# BatteryBoardV1.net
KiCad netlist of a schematic drawn in EAGLE
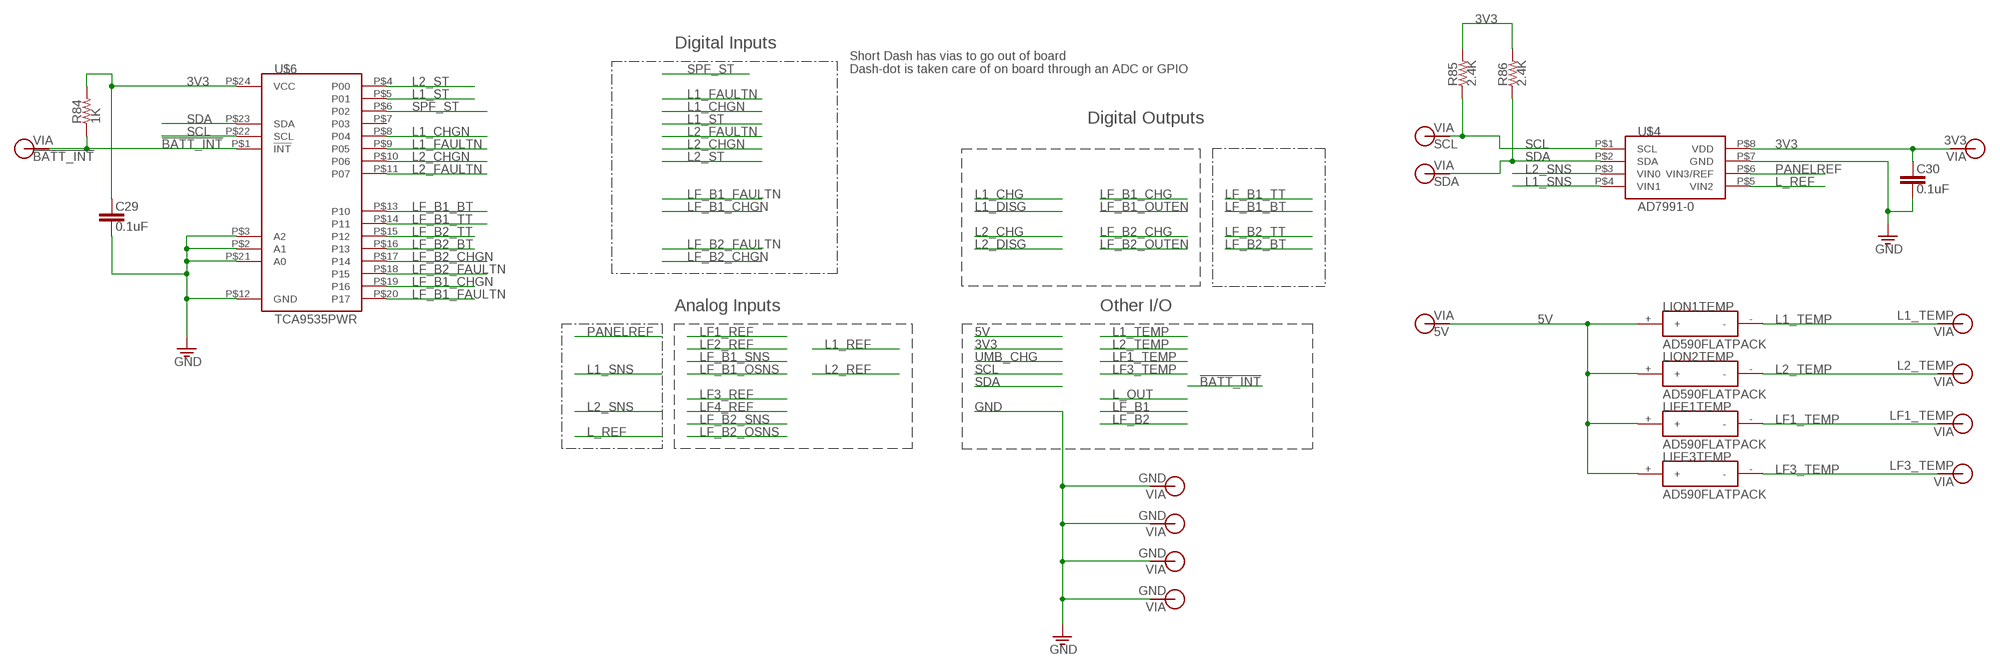
[diagram p0: schematic, sheet 1]
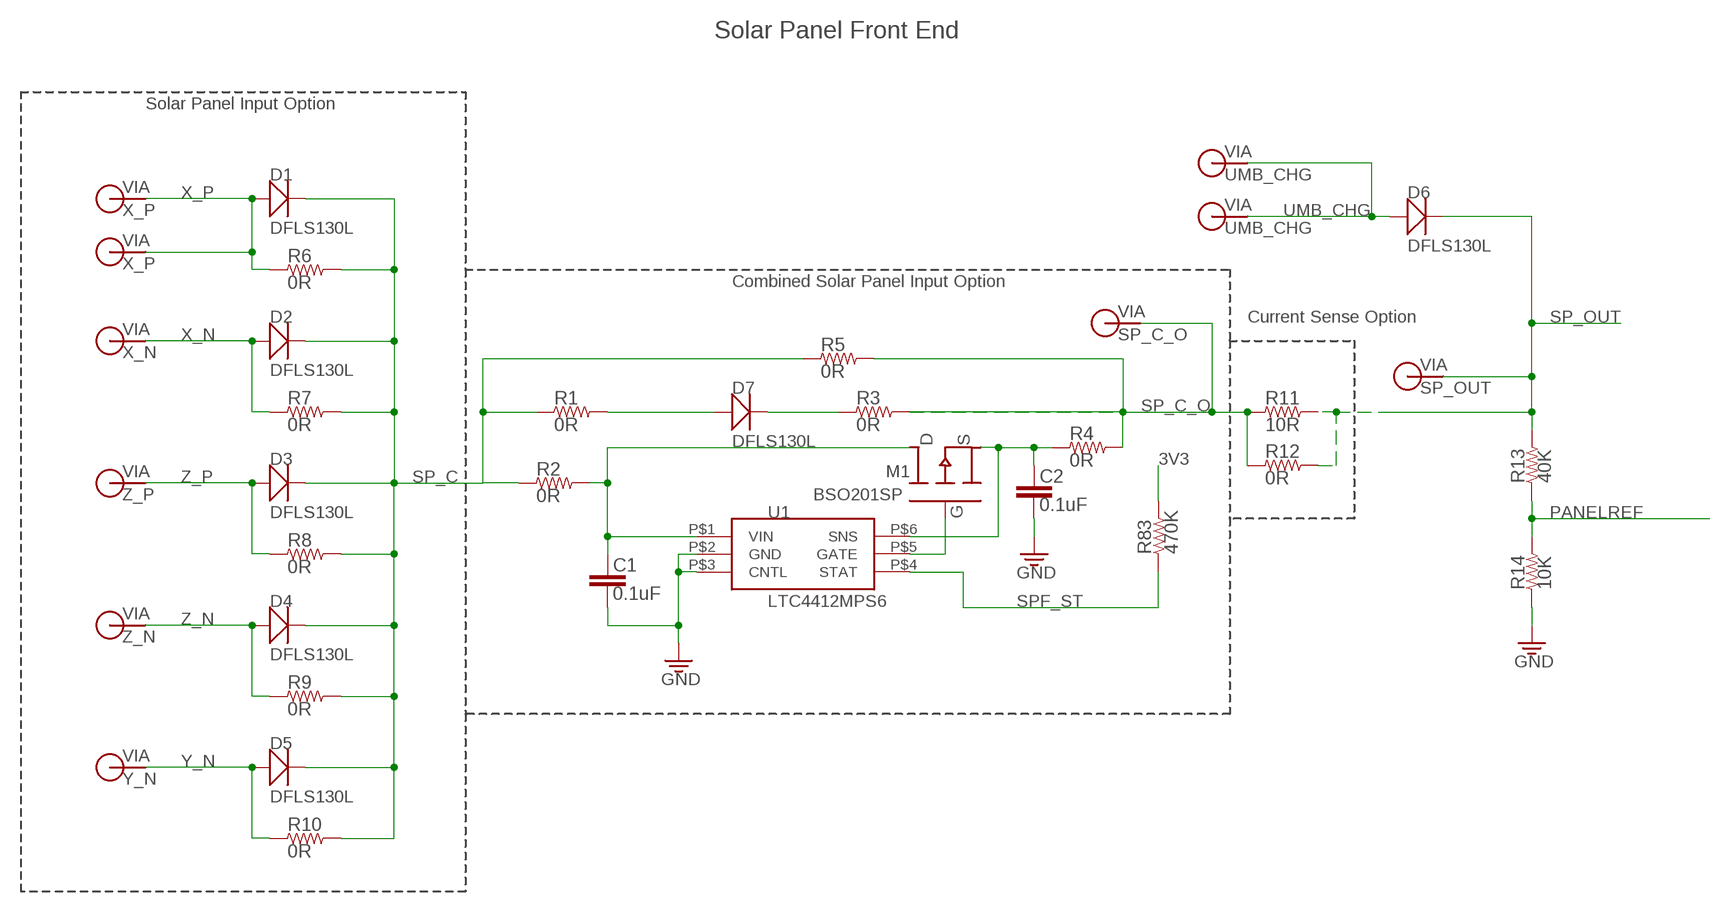
[diagram p1: schematic, sheet 2]
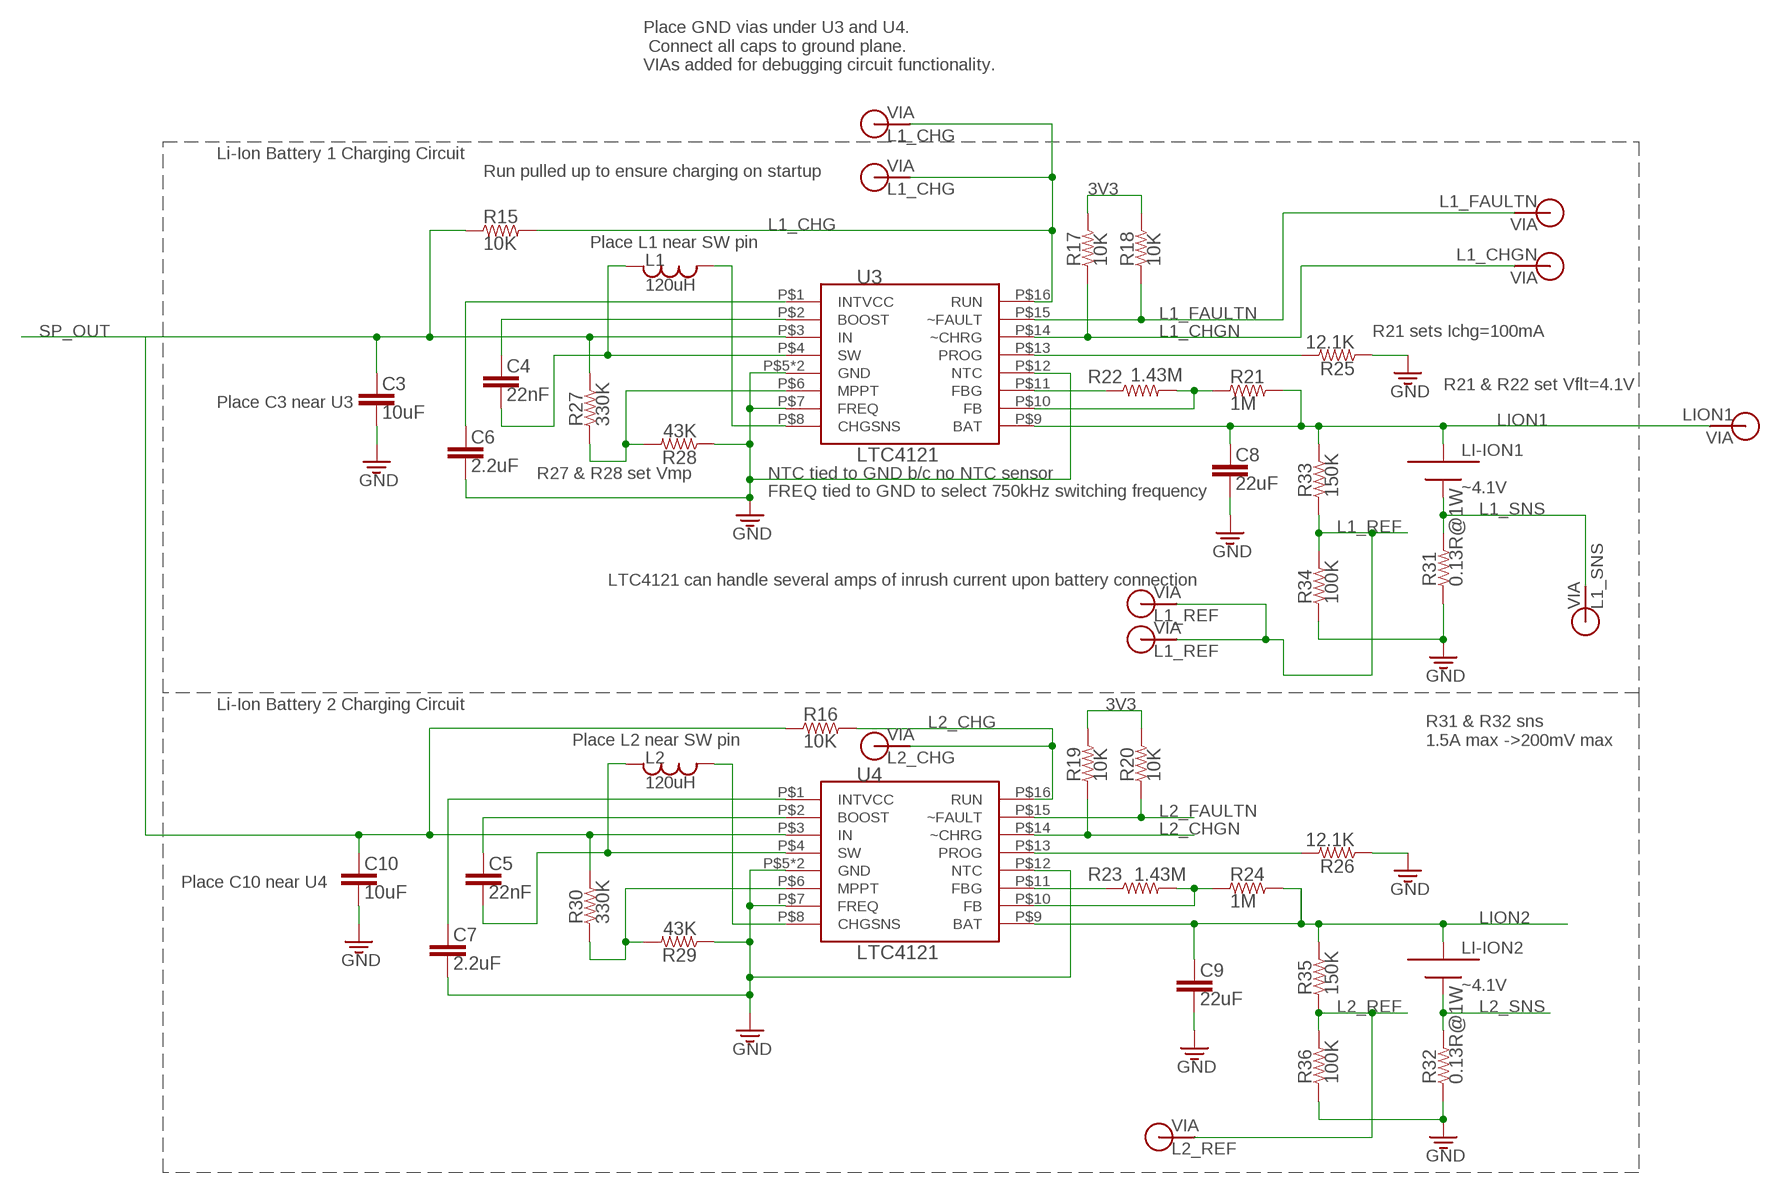
[diagram p2: schematic, sheet 3]
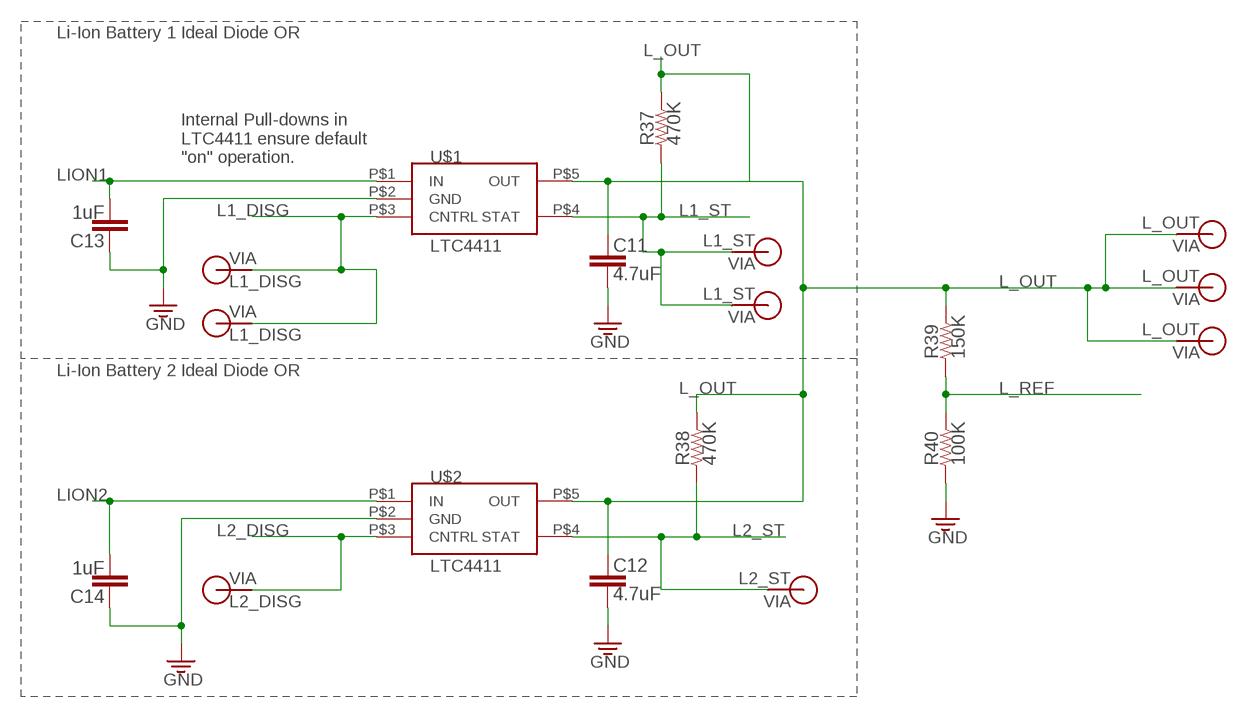
[diagram p3: schematic, sheet 4]
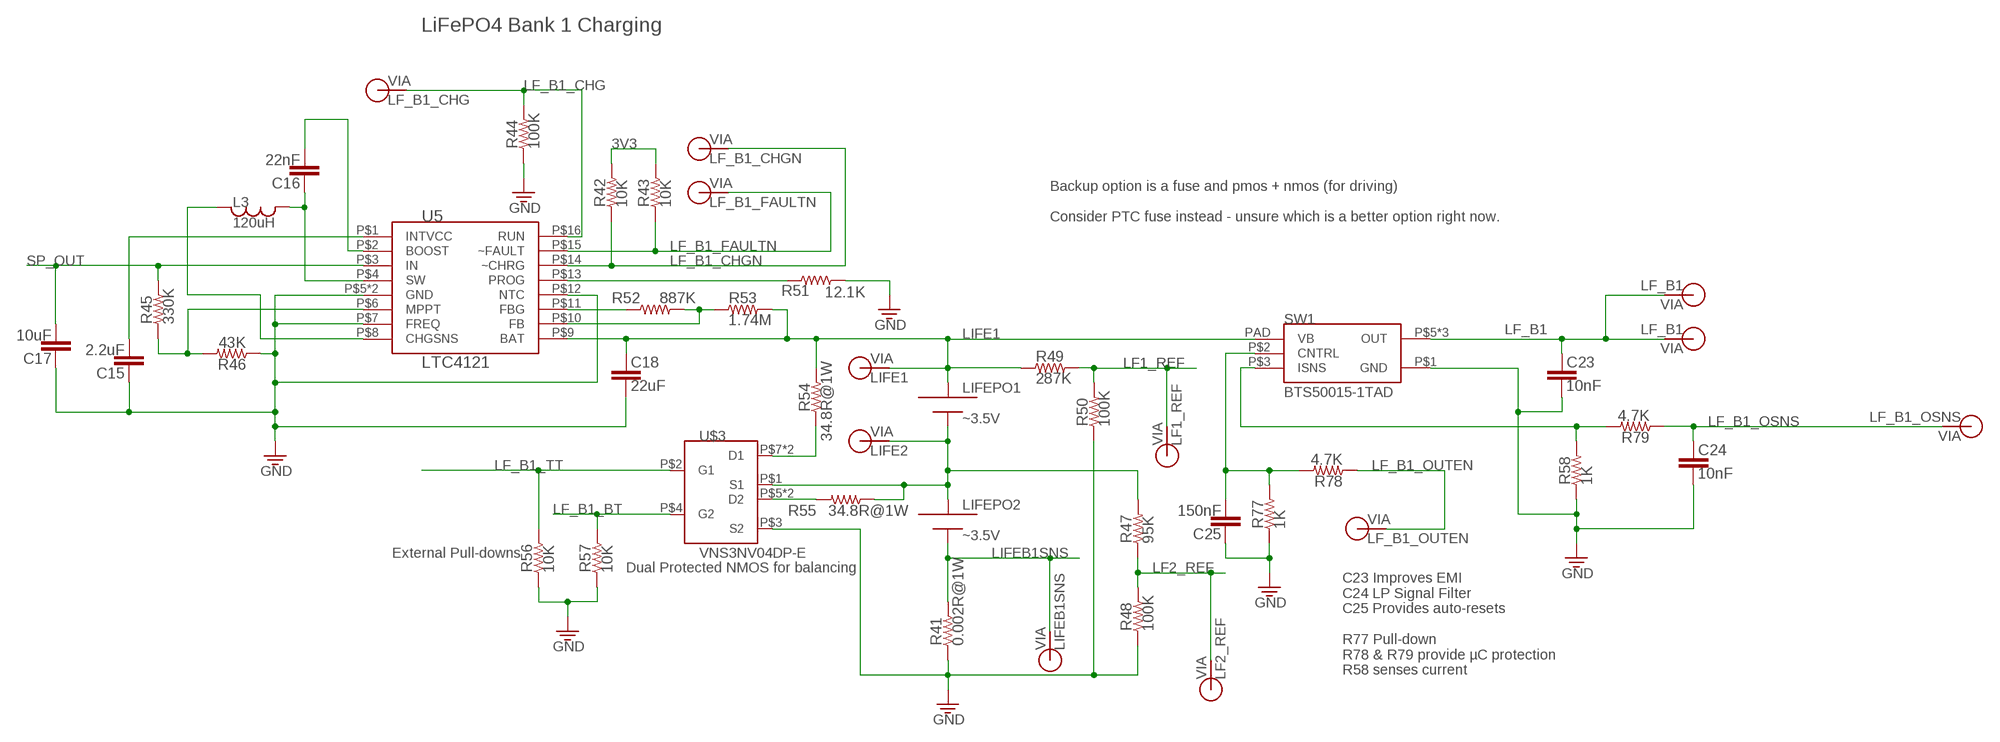
[diagram p4: schematic, sheet 5]
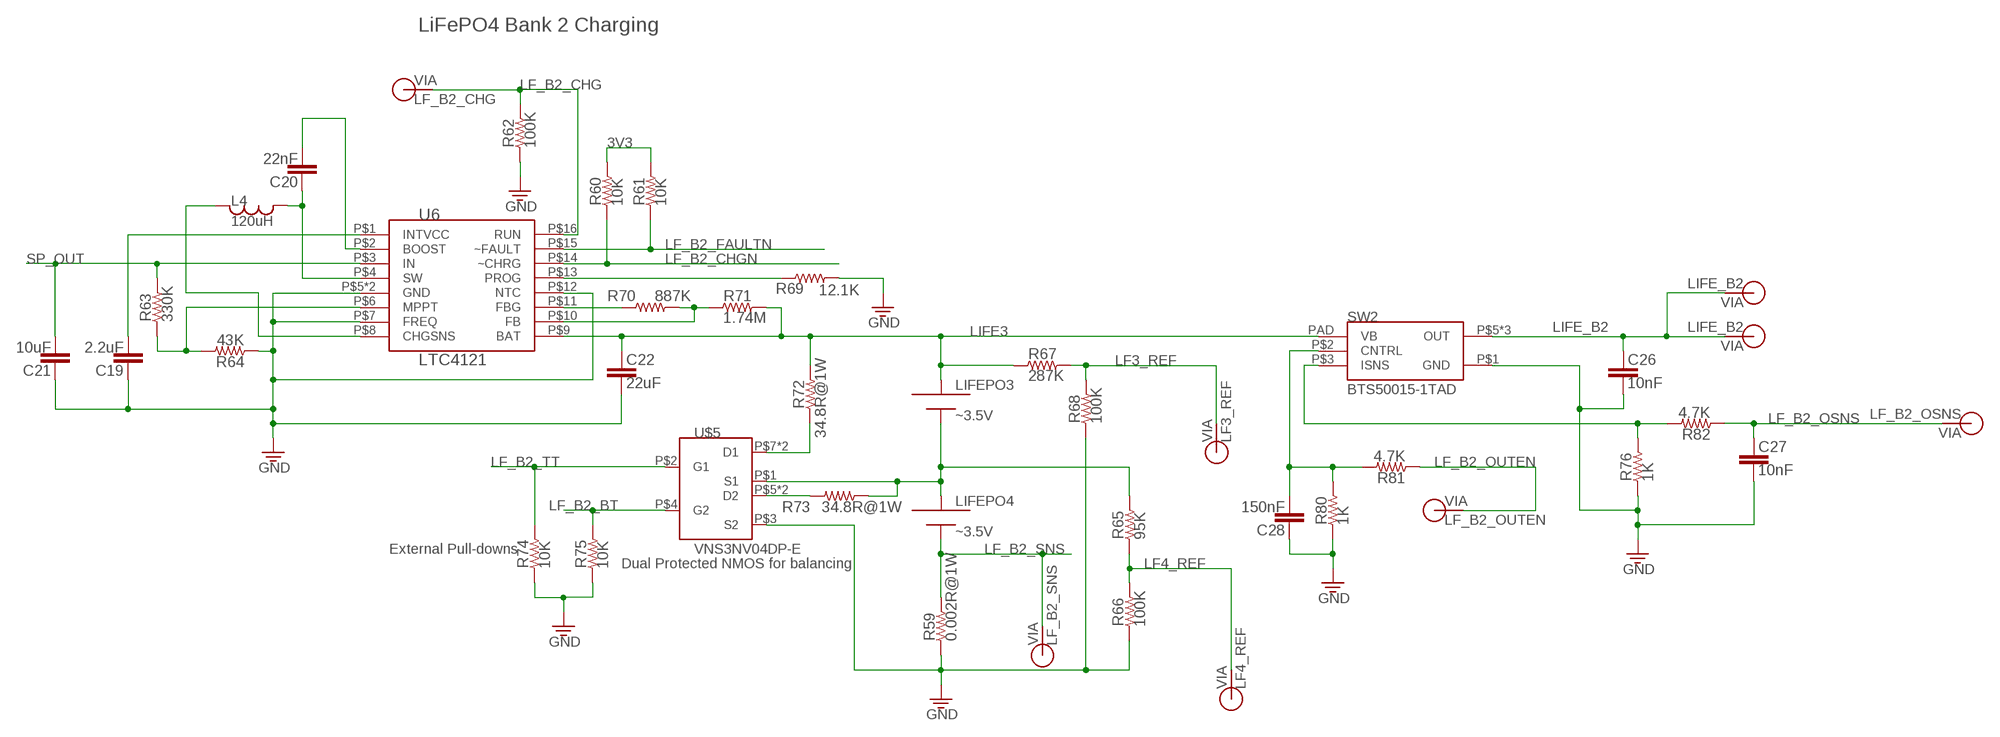
[diagram p5: schematic, sheet 6]

(export (version "E")
  (design (tool "Eeschema 10.0.6"))
  (components
    (comp (ref "C15")
      (value "2.2uF")
      (footprint "eagle-import:0805")
      (libsource (lib "eagle-import") (part "CAP0805"))
    )
    (comp (ref "C16")
      (value "22nF")
      (footprint "eagle-import:0805")
      (libsource (lib "eagle-import") (part "CAP0805"))
    )
    (comp (ref "C17")
      (value "10uF")
      (footprint "eagle-import:0805")
      (libsource (lib "eagle-import") (part "CAP0805"))
    )
    (comp (ref "C18")
      (value "22uF")
      (footprint "eagle-import:0805")
      (libsource (lib "eagle-import") (part "CAP0805"))
    )
    (comp (ref "C23")
      (value "10nF")
      (footprint "eagle-import:0805")
      (libsource (lib "eagle-import") (part "CAP0805"))
    )
    (comp (ref "C24")
      (value "10nF")
      (footprint "eagle-import:0805")
      (libsource (lib "eagle-import") (part "CAP0805"))
    )
    (comp (ref "C25")
      (value "150nF")
      (footprint "eagle-import:0805")
      (libsource (lib "eagle-import") (part "CAP0805"))
    )
    (comp (ref "L3")
      (value "120uH")
      (footprint "eagle-import:1812")
      (libsource (lib "eagle-import") (part "IND1812"))
    )
    (comp (ref "LIFEPO1")
      (value "~3.5V")
      (footprint "eagle-import:EQUISAT-BATTERY-VA")
      (libsource (lib "eagle-import") (part "LIFEPO4VA"))
    )
    (comp (ref "LIFEPO2")
      (value "~3.5V")
      (footprint "eagle-import:EQUISAT-BATTERY-VB")
      (libsource (lib "eagle-import") (part "LIFEPO4VB"))
    )
    (comp (ref "R41")
      (value "0.002R@1W")
      (footprint "eagle-import:1210")
      (libsource (lib "eagle-import") (part "RES1210"))
    )
    (comp (ref "R42")
      (value "10K")
      (footprint "eagle-import:0805")
      (libsource (lib "eagle-import") (part "RES0805"))
    )
    (comp (ref "R43")
      (value "10K")
      (footprint "eagle-import:0805")
      (libsource (lib "eagle-import") (part "RES0805"))
    )
    (comp (ref "R44")
      (value "100K")
      (footprint "eagle-import:0805")
      (libsource (lib "eagle-import") (part "RES0805"))
    )
    (comp (ref "R45")
      (value "330K")
      (footprint "eagle-import:0805")
      (libsource (lib "eagle-import") (part "RES0805"))
    )
    (comp (ref "R46")
      (value "43K")
      (footprint "eagle-import:0805")
      (libsource (lib "eagle-import") (part "RES0805"))
    )
    (comp (ref "R47")
      (value "95K")
      (footprint "eagle-import:0805")
      (libsource (lib "eagle-import") (part "RES0805"))
    )
    (comp (ref "R48")
      (value "100K")
      (footprint "eagle-import:0805")
      (libsource (lib "eagle-import") (part "RES0805"))
    )
    (comp (ref "R49")
      (value "287K")
      (footprint "eagle-import:0805")
      (libsource (lib "eagle-import") (part "RES0805"))
    )
    (comp (ref "R50")
      (value "100K")
      (footprint "eagle-import:0805")
      (libsource (lib "eagle-import") (part "RES0805"))
    )
    (comp (ref "R51")
      (value "12.1K")
      (footprint "eagle-import:0805")
      (libsource (lib "eagle-import") (part "RES0805"))
    )
    (comp (ref "R52")
      (value "887K")
      (footprint "eagle-import:0805")
      (libsource (lib "eagle-import") (part "RES0805"))
    )
    (comp (ref "R53")
      (value "1.74M")
      (footprint "eagle-import:0805")
      (libsource (lib "eagle-import") (part "RES0805"))
    )
    (comp (ref "R54")
      (value "34.8R@1W")
      (footprint "eagle-import:1210")
      (libsource (lib "eagle-import") (part "RES1210"))
    )
    (comp (ref "R55")
      (value "34.8R@1W")
      (footprint "eagle-import:1210")
      (libsource (lib "eagle-import") (part "RES1210"))
    )
    (comp (ref "R56")
      (value "10K")
      (footprint "eagle-import:0805")
      (libsource (lib "eagle-import") (part "RES0805"))
    )
    (comp (ref "R57")
      (value "10K")
      (footprint "eagle-import:0805")
      (libsource (lib "eagle-import") (part "RES0805"))
    )
    (comp (ref "R58")
      (value "1K")
      (footprint "eagle-import:0805")
      (libsource (lib "eagle-import") (part "RES0805"))
    )
    (comp (ref "R77")
      (value "1K")
      (footprint "eagle-import:0805")
      (libsource (lib "eagle-import") (part "RES0805"))
    )
    (comp (ref "R78")
      (value "4.7K")
      (footprint "eagle-import:0805")
      (libsource (lib "eagle-import") (part "RES0805"))
    )
    (comp (ref "R79")
      (value "4.7K")
      (footprint "eagle-import:0805")
      (libsource (lib "eagle-import") (part "RES0805"))
    )
    (comp (ref "SW1")
      (value "BTS50015-1TAD")
      (footprint "eagle-import:TO-263-7-8")
      (libsource (lib "eagle-import") (part "BTS50015-1TAD"))
    )
    (comp (ref "U$3")
      (value "VNS3NV04DP-E")
      (footprint "eagle-import:SO-8")
      (libsource (lib "eagle-import") (part "VNS3NV04DP-E"))
    )
    (comp (ref "U5")
      (value "LTC4121")
      (footprint "eagle-import:QFN-16-PAD")
      (libsource (lib "eagle-import") (part "LTC4121"))
    )
    (comp (ref "V14")
      (value "LIFEB1SNS")
      (footprint "eagle-import:VIA-60MIL")
      (libsource (lib "eagle-import") (part "VIA-60MIL"))
    )
    (comp (ref "V15")
      (value "LF_B1_CHG")
      (footprint "eagle-import:VIA-60MIL")
      (libsource (lib "eagle-import") (part "VIA-60MIL"))
    )
    (comp (ref "V16")
      (value "LIFE2")
      (footprint "eagle-import:VIA-60MIL-SQ")
      (libsource (lib "eagle-import") (part "VIA60MIL-SQ"))
    )
    (comp (ref "V17")
      (value "LIFE1")
      (footprint "eagle-import:VIA-60MIL-SQ")
      (libsource (lib "eagle-import") (part "VIA60MIL-SQ"))
    )
    (comp (ref "V18")
      (value "LF_B1_CHGN")
      (footprint "eagle-import:VIA-60MIL")
      (libsource (lib "eagle-import") (part "VIA-60MIL"))
    )
    (comp (ref "V19")
      (value "LF_B1_FAULTN")
      (footprint "eagle-import:VIA-60MIL")
      (libsource (lib "eagle-import") (part "VIA-60MIL"))
    )
    (comp (ref "V20")
      (value "LF_B1_OUTEN")
      (footprint "eagle-import:VIA-60MIL")
      (libsource (lib "eagle-import") (part "VIA-60MIL"))
    )
    (comp (ref "V21")
      (value "LF_B1")
      (footprint "eagle-import:VIA-120MIL")
      (libsource (lib "eagle-import") (part "VIA-120MIL"))
    )
    (comp (ref "V26")
      (value "LF_B1")
      (footprint "eagle-import:VIA-120MIL")
      (libsource (lib "eagle-import") (part "VIA-120MIL"))
    )
    (comp (ref "V31")
      (value "LF_B1_OSNS")
      (footprint "eagle-import:VIA-60MIL")
      (libsource (lib "eagle-import") (part "VIA-60MIL"))
    )
    (comp (ref "V58")
      (value "LF1_REF")
      (footprint "eagle-import:VIA-60MIL")
      (libsource (lib "eagle-import") (part "VIA-60MIL"))
    )
    (comp (ref "V59")
      (value "LF2_REF")
      (footprint "eagle-import:VIA-60MIL")
      (libsource (lib "eagle-import") (part "VIA-60MIL"))
    )
    (comp (ref "C11")
      (value "4.7uF")
      (footprint "eagle-import:0805")
      (libsource (lib "eagle-import") (part "CAP0805"))
    )
    (comp (ref "C12")
      (value "4.7uF")
      (footprint "eagle-import:0805")
      (libsource (lib "eagle-import") (part "CAP0805"))
    )
    (comp (ref "C13")
      (value "1uF")
      (footprint "eagle-import:0805")
      (libsource (lib "eagle-import") (part "CAP0805"))
    )
    (comp (ref "C14")
      (value "1uF")
      (footprint "eagle-import:0805")
      (libsource (lib "eagle-import") (part "CAP0805"))
    )
    (comp (ref "R37")
      (value "470K")
      (footprint "eagle-import:0805")
      (libsource (lib "eagle-import") (part "RES0805"))
    )
    (comp (ref "R38")
      (value "470K")
      (footprint "eagle-import:0805")
      (libsource (lib "eagle-import") (part "RES0805"))
    )
    (comp (ref "R39")
      (value "150K")
      (footprint "eagle-import:0805")
      (libsource (lib "eagle-import") (part "RES0805"))
    )
    (comp (ref "R40")
      (value "100K")
      (footprint "eagle-import:0805")
      (libsource (lib "eagle-import") (part "RES0805"))
    )
    (comp (ref "U$1")
      (value "LTC4411")
      (footprint "eagle-import:TSOT23-5")
      (libsource (lib "eagle-import") (part "LTC4411"))
    )
    (comp (ref "U$2")
      (value "LTC4411")
      (footprint "eagle-import:TSOT23-5")
      (libsource (lib "eagle-import") (part "LTC4411"))
    )
    (comp (ref "V30")
      (value "L_OUT")
      (footprint "eagle-import:VIA-120MIL")
      (libsource (lib "eagle-import") (part "VIA-120MIL"))
    )
    (comp (ref "V34")
      (value "L1_DISG")
      (footprint "eagle-import:VIA-60MIL")
      (libsource (lib "eagle-import") (part "VIA-60MIL"))
    )
    (comp (ref "V35")
      (value "L2_DISG")
      (footprint "eagle-import:VIA-60MIL")
      (libsource (lib "eagle-import") (part "VIA-60MIL"))
    )
    (comp (ref "V36")
      (value "L1_ST")
      (footprint "eagle-import:VIA-60MIL")
      (libsource (lib "eagle-import") (part "VIA-60MIL"))
    )
    (comp (ref "V38")
      (value "L2_ST")
      (footprint "eagle-import:VIA-60MIL")
      (libsource (lib "eagle-import") (part "VIA-60MIL"))
    )
    (comp (ref "V46")
      (value "L1_DISG")
      (footprint "eagle-import:VIA-60MIL-SQ")
      (libsource (lib "eagle-import") (part "VIA60MIL-SQ"))
    )
    (comp (ref "V47")
      (value "L1_ST")
      (footprint "eagle-import:VIA-60MIL-SQ")
      (libsource (lib "eagle-import") (part "VIA60MIL-SQ"))
    )
    (comp (ref "V48")
      (value "L_OUT")
      (footprint "eagle-import:VIA-60MIL-SQ")
      (libsource (lib "eagle-import") (part "VIA60MIL-SQ"))
    )
    (comp (ref "V54")
      (value "L_OUT")
      (footprint "eagle-import:VIA-120MIL")
      (libsource (lib "eagle-import") (part "VIA-120MIL"))
    )
    (comp (ref "C1")
      (value "0.1uF")
      (footprint "eagle-import:0805")
      (libsource (lib "eagle-import") (part "CAP0805"))
    )
    (comp (ref "C2")
      (value "0.1uF")
      (footprint "eagle-import:0805")
      (libsource (lib "eagle-import") (part "CAP0805"))
    )
    (comp (ref "D1")
      (value "DFLS130L")
      (footprint "eagle-import:PWRDI-123")
      (libsource (lib "eagle-import") (part "DFLS130L"))
    )
    (comp (ref "D2")
      (value "DFLS130L")
      (footprint "eagle-import:PWRDI-123")
      (libsource (lib "eagle-import") (part "DFLS130L"))
    )
    (comp (ref "D3")
      (value "DFLS130L")
      (footprint "eagle-import:PWRDI-123")
      (libsource (lib "eagle-import") (part "DFLS130L"))
    )
    (comp (ref "D4")
      (value "DFLS130L")
      (footprint "eagle-import:PWRDI-123")
      (libsource (lib "eagle-import") (part "DFLS130L"))
    )
    (comp (ref "D5")
      (value "DFLS130L")
      (footprint "eagle-import:PWRDI-123")
      (libsource (lib "eagle-import") (part "DFLS130L"))
    )
    (comp (ref "D6")
      (value "DFLS130L")
      (footprint "eagle-import:PWRDI-123")
      (libsource (lib "eagle-import") (part "DFLS130L"))
    )
    (comp (ref "D7")
      (value "DFLS130L")
      (footprint "eagle-import:PWRDI-123")
      (libsource (lib "eagle-import") (part "DFLS130L"))
    )
    (comp (ref "M1")
      (value "BSO201SP")
      (footprint "eagle-import:SO-8")
      (libsource (lib "eagle-import") (part "BSO201SP"))
    )
    (comp (ref "R1")
      (value "0R")
      (footprint "eagle-import:0805")
      (libsource (lib "eagle-import") (part "RES0805"))
    )
    (comp (ref "R2")
      (value "0R")
      (footprint "eagle-import:0805")
      (libsource (lib "eagle-import") (part "RES0805"))
    )
    (comp (ref "R3")
      (value "0R")
      (footprint "eagle-import:0805")
      (libsource (lib "eagle-import") (part "RES0805"))
    )
    (comp (ref "R4")
      (value "0R")
      (footprint "eagle-import:0805")
      (libsource (lib "eagle-import") (part "RES0805"))
    )
    (comp (ref "R5")
      (value "0R")
      (footprint "eagle-import:0805")
      (libsource (lib "eagle-import") (part "RES0805"))
    )
    (comp (ref "R6")
      (value "0R")
      (footprint "eagle-import:0805")
      (libsource (lib "eagle-import") (part "RES0805"))
    )
    (comp (ref "R7")
      (value "0R")
      (footprint "eagle-import:0805")
      (libsource (lib "eagle-import") (part "RES0805"))
    )
    (comp (ref "R8")
      (value "0R")
      (footprint "eagle-import:0805")
      (libsource (lib "eagle-import") (part "RES0805"))
    )
    (comp (ref "R9")
      (value "0R")
      (footprint "eagle-import:0805")
      (libsource (lib "eagle-import") (part "RES0805"))
    )
    (comp (ref "R10")
      (value "0R")
      (footprint "eagle-import:0805")
      (libsource (lib "eagle-import") (part "RES0805"))
    )
    (comp (ref "R11")
      (value "10R")
      (footprint "eagle-import:0805")
      (libsource (lib "eagle-import") (part "RES0805"))
    )
    (comp (ref "R12")
      (value "0R")
      (footprint "eagle-import:0805")
      (libsource (lib "eagle-import") (part "RES0805"))
    )
    (comp (ref "R13")
      (value "40K")
      (footprint "eagle-import:0805")
      (libsource (lib "eagle-import") (part "RES0805"))
    )
    (comp (ref "R14")
      (value "10K")
      (footprint "eagle-import:0805")
      (libsource (lib "eagle-import") (part "RES0805"))
    )
    (comp (ref "R83")
      (value "470K")
      (footprint "eagle-import:0805")
      (libsource (lib "eagle-import") (part "RES0805"))
    )
    (comp (ref "U1")
      (value "LTC4412MPS6")
      (footprint "eagle-import:TSOT23-6")
      (libsource (lib "eagle-import") (part "LTC4412"))
    )
    (comp (ref "V1")
      (value "UMB_CHG")
      (footprint "eagle-import:VIA-60MIL")
      (libsource (lib "eagle-import") (part "VIA-60MIL"))
    )
    (comp (ref "V2")
      (value "X_P")
      (footprint "eagle-import:VIA-60MIL")
      (libsource (lib "eagle-import") (part "VIA-60MIL"))
    )
    (comp (ref "V3")
      (value "X_N")
      (footprint "eagle-import:VIA-60MIL")
      (libsource (lib "eagle-import") (part "VIA-60MIL"))
    )
    (comp (ref "V4")
      (value "Z_P")
      (footprint "eagle-import:VIA-60MIL")
      (libsource (lib "eagle-import") (part "VIA-60MIL"))
    )
    (comp (ref "V5")
      (value "Z_N")
      (footprint "eagle-import:VIA-60MIL")
      (libsource (lib "eagle-import") (part "VIA-60MIL"))
    )
    (comp (ref "V6")
      (value "Y_N")
      (footprint "eagle-import:VIA-60MIL")
      (libsource (lib "eagle-import") (part "VIA-60MIL"))
    )
    (comp (ref "V7")
      (value "SP_C_O")
      (footprint "eagle-import:VIA-60MIL-SQ")
      (libsource (lib "eagle-import") (part "VIA60MIL-SQ"))
    )
    (comp (ref "V8")
      (value "SP_OUT")
      (footprint "eagle-import:VIA-60MIL-SQ")
      (libsource (lib "eagle-import") (part "VIA60MIL-SQ"))
    )
    (comp (ref "V39")
      (value "UMB_CHG")
      (footprint "eagle-import:VIA-60MIL-SQ")
      (libsource (lib "eagle-import") (part "VIA60MIL-SQ"))
    )
    (comp (ref "V49")
      (value "X_P")
      (footprint "eagle-import:VIA-60MIL-SQ")
      (libsource (lib "eagle-import") (part "VIA60MIL-SQ"))
    )
    (comp (ref "C3")
      (value "10uF")
      (footprint "eagle-import:0805")
      (libsource (lib "eagle-import") (part "CAP0805"))
    )
    (comp (ref "C4")
      (value "22nF")
      (footprint "eagle-import:0805")
      (libsource (lib "eagle-import") (part "CAP0805"))
    )
    (comp (ref "C5")
      (value "22nF")
      (footprint "eagle-import:0805")
      (libsource (lib "eagle-import") (part "CAP0805"))
    )
    (comp (ref "C6")
      (value "2.2uF")
      (footprint "eagle-import:0805")
      (libsource (lib "eagle-import") (part "CAP0805"))
    )
    (comp (ref "C7")
      (value "2.2uF")
      (footprint "eagle-import:0805")
      (libsource (lib "eagle-import") (part "CAP0805"))
    )
    (comp (ref "C8")
      (value "22uF")
      (footprint "eagle-import:0805")
      (libsource (lib "eagle-import") (part "CAP0805"))
    )
    (comp (ref "C9")
      (value "22uF")
      (footprint "eagle-import:0805")
      (libsource (lib "eagle-import") (part "CAP0805"))
    )
    (comp (ref "C10")
      (value "10uF")
      (footprint "eagle-import:0805")
      (libsource (lib "eagle-import") (part "CAP0805"))
    )
    (comp (ref "L1")
      (value "120uH")
      (footprint "eagle-import:1812")
      (libsource (lib "eagle-import") (part "IND1812"))
    )
    (comp (ref "L2")
      (value "120uH")
      (footprint "eagle-import:1812")
      (libsource (lib "eagle-import") (part "IND1812"))
    )
    (comp (ref "LI-ION1")
      (value "~4.1V")
      (footprint "eagle-import:EQUISAT-BATTERY-VA")
      (libsource (lib "eagle-import") (part "LI-ION"))
    )
    (comp (ref "LI-ION2")
      (value "~4.1V")
      (footprint "eagle-import:EQUISAT-BATTERY-VA")
      (libsource (lib "eagle-import") (part "LI-ION"))
    )
    (comp (ref "R15")
      (value "10K")
      (footprint "eagle-import:0805")
      (libsource (lib "eagle-import") (part "RES0805"))
    )
    (comp (ref "R16")
      (value "10K")
      (footprint "eagle-import:0805")
      (libsource (lib "eagle-import") (part "RES0805"))
    )
    (comp (ref "R17")
      (value "10K")
      (footprint "eagle-import:0805")
      (libsource (lib "eagle-import") (part "RES0805"))
    )
    (comp (ref "R18")
      (value "10K")
      (footprint "eagle-import:0805")
      (libsource (lib "eagle-import") (part "RES0805"))
    )
    (comp (ref "R19")
      (value "10K")
      (footprint "eagle-import:0805")
      (libsource (lib "eagle-import") (part "RES0805"))
    )
    (comp (ref "R20")
      (value "10K")
      (footprint "eagle-import:0805")
      (libsource (lib "eagle-import") (part "RES0805"))
    )
    (comp (ref "R21")
      (value "1M")
      (footprint "eagle-import:0805")
      (libsource (lib "eagle-import") (part "RES0805"))
    )
    (comp (ref "R22")
      (value "1.43M")
      (footprint "eagle-import:0805")
      (libsource (lib "eagle-import") (part "RES0805"))
    )
    (comp (ref "R23")
      (value "1.43M")
      (footprint "eagle-import:0805")
      (libsource (lib "eagle-import") (part "RES0805"))
    )
    (comp (ref "R24")
      (value "1M")
      (footprint "eagle-import:0805")
      (libsource (lib "eagle-import") (part "RES0805"))
    )
    (comp (ref "R25")
      (value "12.1K")
      (footprint "eagle-import:0805")
      (libsource (lib "eagle-import") (part "RES0805"))
    )
    (comp (ref "R26")
      (value "12.1K")
      (footprint "eagle-import:0805")
      (libsource (lib "eagle-import") (part "RES0805"))
    )
    (comp (ref "R27")
      (value "330K")
      (footprint "eagle-import:0805")
      (libsource (lib "eagle-import") (part "RES0805"))
    )
    (comp (ref "R28")
      (value "43K")
      (footprint "eagle-import:0805")
      (libsource (lib "eagle-import") (part "RES0805"))
    )
    (comp (ref "R29")
      (value "43K")
      (footprint "eagle-import:0805")
      (libsource (lib "eagle-import") (part "RES0805"))
    )
    (comp (ref "R30")
      (value "330K")
      (footprint "eagle-import:0805")
      (libsource (lib "eagle-import") (part "RES0805"))
    )
    (comp (ref "R31")
      (value "0.13R@1W")
      (footprint "eagle-import:1210")
      (libsource (lib "eagle-import") (part "RES1210"))
    )
    (comp (ref "R32")
      (value "0.13R@1W")
      (footprint "eagle-import:1210")
      (libsource (lib "eagle-import") (part "RES1210"))
    )
    (comp (ref "R33")
      (value "150K")
      (footprint "eagle-import:0805")
      (libsource (lib "eagle-import") (part "RES0805"))
    )
    (comp (ref "R34")
      (value "100K")
      (footprint "eagle-import:0805")
      (libsource (lib "eagle-import") (part "RES0805"))
    )
    (comp (ref "R35")
      (value "150K")
      (footprint "eagle-import:0805")
      (libsource (lib "eagle-import") (part "RES0805"))
    )
    (comp (ref "R36")
      (value "100K")
      (footprint "eagle-import:0805")
      (libsource (lib "eagle-import") (part "RES0805"))
    )
    (comp (ref "U3")
      (value "LTC4121")
      (footprint "eagle-import:QFN-16-PAD")
      (libsource (lib "eagle-import") (part "LTC4121"))
    )
    (comp (ref "U4")
      (value "LTC4121")
      (footprint "eagle-import:QFN-16-PAD")
      (libsource (lib "eagle-import") (part "LTC4121"))
    )
    (comp (ref "V10")
      (value "L1_CHG")
      (footprint "eagle-import:VIA-60MIL")
      (libsource (lib "eagle-import") (part "VIA-60MIL"))
    )
    (comp (ref "V25")
      (value "L1_REF")
      (footprint "eagle-import:VIA-60MIL")
      (libsource (lib "eagle-import") (part "VIA-60MIL"))
    )
    (comp (ref "V29")
      (value "L2_REF")
      (footprint "eagle-import:VIA-60MIL")
      (libsource (lib "eagle-import") (part "VIA-60MIL"))
    )
    (comp (ref "V33")
      (value "L2_CHG")
      (footprint "eagle-import:VIA-60MIL")
      (libsource (lib "eagle-import") (part "VIA-60MIL"))
    )
    (comp (ref "V40")
      (value "L1_CHG")
      (footprint "eagle-import:VIA-60MIL-SQ")
      (libsource (lib "eagle-import") (part "VIA60MIL-SQ"))
    )
    (comp (ref "V41")
      (value "L1_FAULTN")
      (footprint "eagle-import:VIA-60MIL-SQ")
      (libsource (lib "eagle-import") (part "VIA60MIL-SQ"))
    )
    (comp (ref "V42")
      (value "L1_CHGN")
      (footprint "eagle-import:VIA-60MIL-SQ")
      (libsource (lib "eagle-import") (part "VIA60MIL-SQ"))
    )
    (comp (ref "V43")
      (value "L1_SNS")
      (footprint "eagle-import:VIA-60MIL-SQ")
      (libsource (lib "eagle-import") (part "VIA60MIL-SQ"))
    )
    (comp (ref "V44")
      (value "L1_REF")
      (footprint "eagle-import:VIA-60MIL-SQ")
      (libsource (lib "eagle-import") (part "VIA60MIL-SQ"))
    )
    (comp (ref "V45")
      (value "LION1")
      (footprint "eagle-import:VIA-60MIL-SQ")
      (libsource (lib "eagle-import") (part "VIA60MIL-SQ"))
    )
    (comp (ref "C29")
      (value "0.1uF")
      (footprint "eagle-import:0805")
      (libsource (lib "eagle-import") (part "CAP0805"))
    )
    (comp (ref "C30")
      (value "0.1uF")
      (footprint "eagle-import:0805")
      (libsource (lib "eagle-import") (part "CAP0805"))
    )
    (comp (ref "LIFE1TEMP")
      (value "AD590FLATPACK")
      (footprint "eagle-import:FLATPACK")
      (libsource (lib "eagle-import") (part "AD590FLATPACK"))
    )
    (comp (ref "LIFE3TEMP")
      (value "AD590FLATPACK")
      (footprint "eagle-import:FLATPACK")
      (libsource (lib "eagle-import") (part "AD590FLATPACK"))
    )
    (comp (ref "LION1TEMP")
      (value "AD590FLATPACK")
      (footprint "eagle-import:FLATPACK")
      (libsource (lib "eagle-import") (part "AD590FLATPACK"))
    )
    (comp (ref "LION2TEMP")
      (value "AD590FLATPACK")
      (footprint "eagle-import:FLATPACK")
      (libsource (lib "eagle-import") (part "AD590FLATPACK"))
    )
    (comp (ref "R84")
      (value "1K")
      (footprint "eagle-import:0805")
      (libsource (lib "eagle-import") (part "RES0805"))
    )
    (comp (ref "R85")
      (value "2.4K")
      (footprint "eagle-import:0805")
      (libsource (lib "eagle-import") (part "RES0805"))
    )
    (comp (ref "R86")
      (value "2.4K")
      (footprint "eagle-import:0805")
      (libsource (lib "eagle-import") (part "RES0805"))
    )
    (comp (ref "U$4")
      (value "AD7991-0")
      (footprint "eagle-import:SOT-23-8")
      (libsource (lib "eagle-import") (part "AD7991-0"))
    )
    (comp (ref "U$6")
      (value "TCA9535PWR")
      (footprint "eagle-import:TSSOP-24")
      (libsource (lib "eagle-import") (part "TCA9535PWR"))
    )
    (comp (ref "V9")
      (value "5V")
      (footprint "eagle-import:VIA-60MIL")
      (libsource (lib "eagle-import") (part "VIA-60MIL"))
    )
    (comp (ref "V11")
      (value "!BATT_INT!")
      (footprint "eagle-import:VIA-60MIL")
      (libsource (lib "eagle-import") (part "VIA-60MIL"))
    )
    (comp (ref "V12")
      (value "GND")
      (footprint "eagle-import:VIA-60MIL-SQ")
      (libsource (lib "eagle-import") (part "VIA60MIL-SQ"))
    )
    (comp (ref "V13")
      (value "GND")
      (footprint "eagle-import:VIA-120MIL")
      (libsource (lib "eagle-import") (part "VIA-120MIL"))
    )
    (comp (ref "V22")
      (value "GND")
      (footprint "eagle-import:VIA-120MIL")
      (libsource (lib "eagle-import") (part "VIA-120MIL"))
    )
    (comp (ref "V23")
      (value "GND")
      (footprint "eagle-import:VIA-120MIL")
      (libsource (lib "eagle-import") (part "VIA-120MIL"))
    )
    (comp (ref "V24")
      (value "L1_TEMP")
      (footprint "eagle-import:VIA-60MIL")
      (libsource (lib "eagle-import") (part "VIA-60MIL"))
    )
    (comp (ref "V32")
      (value "L2_TEMP")
      (footprint "eagle-import:VIA-60MIL")
      (libsource (lib "eagle-import") (part "VIA-60MIL"))
    )
    (comp (ref "V37")
      (value "LF1_TEMP")
      (footprint "eagle-import:VIA-60MIL")
      (libsource (lib "eagle-import") (part "VIA-60MIL"))
    )
    (comp (ref "V50")
      (value "LF3_TEMP")
      (footprint "eagle-import:VIA-60MIL")
      (libsource (lib "eagle-import") (part "VIA-60MIL"))
    )
    (comp (ref "V51")
      (value "3V3")
      (footprint "eagle-import:VIA-60MIL")
      (libsource (lib "eagle-import") (part "VIA-60MIL"))
    )
    (comp (ref "V52")
      (value "SCL")
      (footprint "eagle-import:VIA-60MIL")
      (libsource (lib "eagle-import") (part "VIA-60MIL"))
    )
    (comp (ref "V53")
      (value "SDA")
      (footprint "eagle-import:VIA-60MIL")
      (libsource (lib "eagle-import") (part "VIA-60MIL"))
    )
    (comp (ref "C19")
      (value "2.2uF")
      (footprint "eagle-import:0805")
      (libsource (lib "eagle-import") (part "CAP0805"))
    )
    (comp (ref "C20")
      (value "22nF")
      (footprint "eagle-import:0805")
      (libsource (lib "eagle-import") (part "CAP0805"))
    )
    (comp (ref "C21")
      (value "10uF")
      (footprint "eagle-import:0805")
      (libsource (lib "eagle-import") (part "CAP0805"))
    )
    (comp (ref "C22")
      (value "22uF")
      (footprint "eagle-import:0805")
      (libsource (lib "eagle-import") (part "CAP0805"))
    )
    (comp (ref "C26")
      (value "10nF")
      (footprint "eagle-import:0805")
      (libsource (lib "eagle-import") (part "CAP0805"))
    )
    (comp (ref "C27")
      (value "10nF")
      (footprint "eagle-import:0805")
      (libsource (lib "eagle-import") (part "CAP0805"))
    )
    (comp (ref "C28")
      (value "150nF")
      (footprint "eagle-import:0805")
      (libsource (lib "eagle-import") (part "CAP0805"))
    )
    (comp (ref "L4")
      (value "120uH")
      (footprint "eagle-import:1812")
      (libsource (lib "eagle-import") (part "IND1812"))
    )
    (comp (ref "LIFEPO3")
      (value "~3.5V")
      (footprint "eagle-import:EQUISAT-BATTERY-VA")
      (libsource (lib "eagle-import") (part "LIFEPO4VA"))
    )
    (comp (ref "LIFEPO4")
      (value "~3.5V")
      (footprint "eagle-import:EQUISAT-BATTERY-VB")
      (libsource (lib "eagle-import") (part "LIFEPO4VB"))
    )
    (comp (ref "R59")
      (value "0.002R@1W")
      (footprint "eagle-import:1210")
      (libsource (lib "eagle-import") (part "RES1210"))
    )
    (comp (ref "R60")
      (value "10K")
      (footprint "eagle-import:0805")
      (libsource (lib "eagle-import") (part "RES0805"))
    )
    (comp (ref "R61")
      (value "10K")
      (footprint "eagle-import:0805")
      (libsource (lib "eagle-import") (part "RES0805"))
    )
    (comp (ref "R62")
      (value "100K")
      (footprint "eagle-import:0805")
      (libsource (lib "eagle-import") (part "RES0805"))
    )
    (comp (ref "R63")
      (value "330K")
      (footprint "eagle-import:0805")
      (libsource (lib "eagle-import") (part "RES0805"))
    )
    (comp (ref "R64")
      (value "43K")
      (footprint "eagle-import:0805")
      (libsource (lib "eagle-import") (part "RES0805"))
    )
    (comp (ref "R65")
      (value "95K")
      (footprint "eagle-import:0805")
      (libsource (lib "eagle-import") (part "RES0805"))
    )
    (comp (ref "R66")
      (value "100K")
      (footprint "eagle-import:0805")
      (libsource (lib "eagle-import") (part "RES0805"))
    )
    (comp (ref "R67")
      (value "287K")
      (footprint "eagle-import:0805")
      (libsource (lib "eagle-import") (part "RES0805"))
    )
    (comp (ref "R68")
      (value "100K")
      (footprint "eagle-import:0805")
      (libsource (lib "eagle-import") (part "RES0805"))
    )
    (comp (ref "R69")
      (value "12.1K")
      (footprint "eagle-import:0805")
      (libsource (lib "eagle-import") (part "RES0805"))
    )
    (comp (ref "R70")
      (value "887K")
      (footprint "eagle-import:0805")
      (libsource (lib "eagle-import") (part "RES0805"))
    )
    (comp (ref "R71")
      (value "1.74M")
      (footprint "eagle-import:0805")
      (libsource (lib "eagle-import") (part "RES0805"))
    )
    (comp (ref "R72")
      (value "34.8R@1W")
      (footprint "eagle-import:1210")
      (libsource (lib "eagle-import") (part "RES1210"))
    )
    (comp (ref "R73")
      (value "34.8R@1W")
      (footprint "eagle-import:1210")
      (libsource (lib "eagle-import") (part "RES1210"))
    )
    (comp (ref "R74")
      (value "10K")
      (footprint "eagle-import:0805")
      (libsource (lib "eagle-import") (part "RES0805"))
    )
    (comp (ref "R75")
      (value "10K")
      (footprint "eagle-import:0805")
      (libsource (lib "eagle-import") (part "RES0805"))
    )
    (comp (ref "R76")
      (value "1K")
      (footprint "eagle-import:0805")
      (libsource (lib "eagle-import") (part "RES0805"))
    )
    (comp (ref "R80")
      (value "1K")
      (footprint "eagle-import:0805")
      (libsource (lib "eagle-import") (part "RES0805"))
    )
    (comp (ref "R81")
      (value "4.7K")
      (footprint "eagle-import:0805")
      (libsource (lib "eagle-import") (part "RES0805"))
    )
    (comp (ref "R82")
      (value "4.7K")
      (footprint "eagle-import:0805")
      (libsource (lib "eagle-import") (part "RES0805"))
    )
    (comp (ref "SW2")
      (value "BTS50015-1TAD")
      (footprint "eagle-import:TO-263-7-8")
      (libsource (lib "eagle-import") (part "BTS50015-1TAD"))
    )
    (comp (ref "U$5")
      (value "VNS3NV04DP-E")
      (footprint "eagle-import:SO-8")
      (libsource (lib "eagle-import") (part "VNS3NV04DP-E"))
    )
    (comp (ref "U6")
      (value "LTC4121")
      (footprint "eagle-import:QFN-16-PAD")
      (libsource (lib "eagle-import") (part "LTC4121"))
    )
    (comp (ref "V27")
      (value "LIFE_B2")
      (footprint "eagle-import:VIA-120MIL")
      (libsource (lib "eagle-import") (part "VIA-120MIL"))
    )
    (comp (ref "V28")
      (value "LIFE_B2")
      (footprint "eagle-import:VIA-120MIL")
      (libsource (lib "eagle-import") (part "VIA-120MIL"))
    )
    (comp (ref "V56")
      (value "LF_B2_OUTEN")
      (footprint "eagle-import:VIA-60MIL")
      (libsource (lib "eagle-import") (part "VIA-60MIL"))
    )
    (comp (ref "V57")
      (value "LF_B2_CHG")
      (footprint "eagle-import:VIA-60MIL")
      (libsource (lib "eagle-import") (part "VIA-60MIL"))
    )
    (comp (ref "V60")
      (value "LF_B2_SNS")
      (footprint "eagle-import:VIA-60MIL")
      (libsource (lib "eagle-import") (part "VIA-60MIL"))
    )
    (comp (ref "V61")
      (value "LF4_REF")
      (footprint "eagle-import:VIA-60MIL")
      (libsource (lib "eagle-import") (part "VIA-60MIL"))
    )
    (comp (ref "V62")
      (value "LF3_REF")
      (footprint "eagle-import:VIA-60MIL")
      (libsource (lib "eagle-import") (part "VIA-60MIL"))
    )
    (comp (ref "V63")
      (value "LF_B2_OSNS")
      (footprint "eagle-import:VIA-60MIL")
      (libsource (lib "eagle-import") (part "VIA-60MIL"))
    )
  )
  (nets
    (net (code "1") (name "3V3") (class "Default")
      (node (ref "C29") (pin "1") (pinfunction "P$1_1") (pintype "passive"))
      (node (ref "C30") (pin "1") (pinfunction "P$1_1") (pintype "passive"))
      (node (ref "R17") (pin "2") (pinfunction "2_2") (pintype "passive"))
      (node (ref "R18") (pin "2") (pinfunction "2_2") (pintype "passive"))
      (node (ref "R19") (pin "2") (pinfunction "2_2") (pintype "passive"))
      (node (ref "R20") (pin "2") (pinfunction "2_2") (pintype "passive"))
      (node (ref "R42") (pin "2") (pinfunction "2_2") (pintype "passive"))
      (node (ref "R43") (pin "2") (pinfunction "2_2") (pintype "passive"))
      (node (ref "R60") (pin "2") (pinfunction "2_2") (pintype "passive"))
      (node (ref "R61") (pin "2") (pinfunction "2_2") (pintype "passive"))
      (node (ref "R83") (pin "2") (pinfunction "2_2") (pintype "passive"))
      (node (ref "R84") (pin "2") (pinfunction "2_2") (pintype "passive"))
      (node (ref "R85") (pin "2") (pinfunction "2_2") (pintype "passive"))
      (node (ref "R86") (pin "2") (pinfunction "2_2") (pintype "passive"))
      (node (ref "U$4") (pin "P$8") (pinfunction "VDD_P$8") (pintype "bidirectional"))
      (node (ref "U$6") (pin "P$24") (pinfunction "VCC_P$24") (pintype "power_in"))
      (node (ref "V51") (pin "P$1") (pinfunction "P$1_P$1") (pintype "bidirectional"))
    )
    (net (code "2") (name "5V") (class "Default")
      (node (ref "LIFE1TEMP") (pin "+") (pinfunction "+_+") (pintype "bidirectional"))
      (node (ref "LIFE3TEMP") (pin "+") (pinfunction "+_+") (pintype "bidirectional"))
      (node (ref "LION1TEMP") (pin "+") (pinfunction "+_+") (pintype "bidirectional"))
      (node (ref "LION2TEMP") (pin "+") (pinfunction "+_+") (pintype "bidirectional"))
      (node (ref "V9") (pin "P$1") (pinfunction "P$1_P$1") (pintype "bidirectional"))
    )
    (net (code "3") (name "GND") (class "Default")
      (node (ref "C1") (pin "2") (pinfunction "P$2_2") (pintype "passive"))
      (node (ref "C10") (pin "2") (pinfunction "P$2_2") (pintype "passive"))
      (node (ref "C11") (pin "2") (pinfunction "P$2_2") (pintype "passive"))
      (node (ref "C12") (pin "2") (pinfunction "P$2_2") (pintype "passive"))
      (node (ref "C13") (pin "1") (pinfunction "P$1_1") (pintype "passive"))
      (node (ref "C14") (pin "1") (pinfunction "P$1_1") (pintype "passive"))
      (node (ref "C15") (pin "1") (pinfunction "P$1_1") (pintype "passive"))
      (node (ref "C17") (pin "1") (pinfunction "P$1_1") (pintype "passive"))
      (node (ref "C18") (pin "2") (pinfunction "P$2_2") (pintype "passive"))
      (node (ref "C19") (pin "1") (pinfunction "P$1_1") (pintype "passive"))
      (node (ref "C2") (pin "2") (pinfunction "P$2_2") (pintype "passive"))
      (node (ref "C21") (pin "1") (pinfunction "P$1_1") (pintype "passive"))
      (node (ref "C22") (pin "2") (pinfunction "P$2_2") (pintype "passive"))
      (node (ref "C23") (pin "2") (pinfunction "P$2_2") (pintype "passive"))
      (node (ref "C24") (pin "2") (pinfunction "P$2_2") (pintype "passive"))
      (node (ref "C25") (pin "1") (pinfunction "P$1_1") (pintype "passive"))
      (node (ref "C26") (pin "2") (pinfunction "P$2_2") (pintype "passive"))
      (node (ref "C27") (pin "2") (pinfunction "P$2_2") (pintype "passive"))
      (node (ref "C28") (pin "1") (pinfunction "P$1_1") (pintype "passive"))
      (node (ref "C29") (pin "2") (pinfunction "P$2_2") (pintype "passive"))
      (node (ref "C3") (pin "2") (pinfunction "P$2_2") (pintype "passive"))
      (node (ref "C30") (pin "2") (pinfunction "P$2_2") (pintype "passive"))
      (node (ref "C6") (pin "2") (pinfunction "P$2_2") (pintype "passive"))
      (node (ref "C7") (pin "2") (pinfunction "P$2_2") (pintype "passive"))
      (node (ref "C8") (pin "2") (pinfunction "P$2_2") (pintype "passive"))
      (node (ref "C9") (pin "2") (pinfunction "P$2_2") (pintype "passive"))
      (node (ref "R14") (pin "1") (pinfunction "1_1") (pintype "passive"))
      (node (ref "R25") (pin "1") (pinfunction "1_1") (pintype "passive"))
      (node (ref "R26") (pin "1") (pinfunction "1_1") (pintype "passive"))
      (node (ref "R28") (pin "1") (pinfunction "1_1") (pintype "passive"))
      (node (ref "R29") (pin "1") (pinfunction "1_1") (pintype "passive"))
      (node (ref "R31") (pin "P$1") (pinfunction "1_P$1") (pintype "passive"))
      (node (ref "R32") (pin "P$1") (pinfunction "1_P$1") (pintype "passive"))
      (node (ref "R34") (pin "1") (pinfunction "1_1") (pintype "passive"))
      (node (ref "R36") (pin "1") (pinfunction "1_1") (pintype "passive"))
      (node (ref "R40") (pin "1") (pinfunction "1_1") (pintype "passive"))
      (node (ref "R41") (pin "P$1") (pinfunction "1_P$1") (pintype "passive"))
      (node (ref "R44") (pin "1") (pinfunction "1_1") (pintype "passive"))
      (node (ref "R46") (pin "1") (pinfunction "1_1") (pintype "passive"))
      (node (ref "R48") (pin "1") (pinfunction "1_1") (pintype "passive"))
      (node (ref "R50") (pin "1") (pinfunction "1_1") (pintype "passive"))
      (node (ref "R51") (pin "2") (pinfunction "2_2") (pintype "passive"))
      (node (ref "R56") (pin "1") (pinfunction "1_1") (pintype "passive"))
      (node (ref "R57") (pin "1") (pinfunction "1_1") (pintype "passive"))
      (node (ref "R58") (pin "1") (pinfunction "1_1") (pintype "passive"))
      (node (ref "R59") (pin "P$1") (pinfunction "1_P$1") (pintype "passive"))
      (node (ref "R62") (pin "1") (pinfunction "1_1") (pintype "passive"))
      (node (ref "R64") (pin "1") (pinfunction "1_1") (pintype "passive"))
      (node (ref "R66") (pin "1") (pinfunction "1_1") (pintype "passive"))
      (node (ref "R68") (pin "1") (pinfunction "1_1") (pintype "passive"))
      (node (ref "R69") (pin "2") (pinfunction "2_2") (pintype "passive"))
      (node (ref "R74") (pin "1") (pinfunction "1_1") (pintype "passive"))
      (node (ref "R75") (pin "1") (pinfunction "1_1") (pintype "passive"))
      (node (ref "R76") (pin "1") (pinfunction "1_1") (pintype "passive"))
      (node (ref "R77") (pin "1") (pinfunction "1_1") (pintype "passive"))
      (node (ref "R80") (pin "1") (pinfunction "1_1") (pintype "passive"))
      (node (ref "SW1") (pin "P$1") (pinfunction "GND_P$1") (pintype "bidirectional"))
      (node (ref "SW2") (pin "P$1") (pinfunction "GND_P$1") (pintype "bidirectional"))
      (node (ref "U$1") (pin "P$2") (pinfunction "GND_P$2") (pintype "bidirectional"))
      (node (ref "U$2") (pin "P$2") (pinfunction "GND_P$2") (pintype "bidirectional"))
      (node (ref "U$3") (pin "P$3") (pinfunction "S2_P$3") (pintype "bidirectional"))
      (node (ref "U$4") (pin "P$7") (pinfunction "GND_P$7") (pintype "bidirectional"))
      (node (ref "U$5") (pin "P$3") (pinfunction "S2_P$3") (pintype "bidirectional"))
      (node (ref "U$6") (pin "P$12") (pinfunction "GND_P$12") (pintype "power_in"))
      (node (ref "U$6") (pin "P$2") (pinfunction "A1_P$2") (pintype "bidirectional"))
      (node (ref "U$6") (pin "P$21") (pinfunction "A0_P$21") (pintype "bidirectional"))
      (node (ref "U$6") (pin "P$3") (pinfunction "A2_P$3") (pintype "bidirectional"))
      (node (ref "U1") (pin "P$2") (pinfunction "GND_P$2") (pintype "bidirectional"))
      (node (ref "U1") (pin "P$3") (pinfunction "CNTL_P$3") (pintype "bidirectional"))
      (node (ref "U3") (pin "P$12") (pinfunction "NTC_P$12") (pintype "bidirectional"))
      (node (ref "U3") (pin "P$17") (pinfunction "GND_P$17") (pintype "bidirectional"))
      (node (ref "U3") (pin "P$5") (pinfunction "GND_P$5") (pintype "bidirectional"))
      (node (ref "U3") (pin "P$7") (pinfunction "FREQ_P$7") (pintype "bidirectional"))
      (node (ref "U4") (pin "P$12") (pinfunction "NTC_P$12") (pintype "bidirectional"))
      (node (ref "U4") (pin "P$17") (pinfunction "GND_P$17") (pintype "bidirectional"))
      (node (ref "U4") (pin "P$5") (pinfunction "GND_P$5") (pintype "bidirectional"))
      (node (ref "U4") (pin "P$7") (pinfunction "FREQ_P$7") (pintype "bidirectional"))
      (node (ref "U5") (pin "P$12") (pinfunction "NTC_P$12") (pintype "bidirectional"))
      (node (ref "U5") (pin "P$17") (pinfunction "GND_P$17") (pintype "bidirectional"))
      (node (ref "U5") (pin "P$5") (pinfunction "GND_P$5") (pintype "bidirectional"))
      (node (ref "U5") (pin "P$7") (pinfunction "FREQ_P$7") (pintype "bidirectional"))
      (node (ref "U6") (pin "P$12") (pinfunction "NTC_P$12") (pintype "bidirectional"))
      (node (ref "U6") (pin "P$17") (pinfunction "GND_P$17") (pintype "bidirectional"))
      (node (ref "U6") (pin "P$5") (pinfunction "GND_P$5") (pintype "bidirectional"))
      (node (ref "U6") (pin "P$7") (pinfunction "FREQ_P$7") (pintype "bidirectional"))
      (node (ref "V12") (pin "P$1") (pinfunction "P$1_P$1") (pintype "bidirectional"))
      (node (ref "V13") (pin "P$1") (pinfunction "P$1_P$1") (pintype "bidirectional"))
      (node (ref "V22") (pin "P$1") (pinfunction "P$1_P$1") (pintype "bidirectional"))
      (node (ref "V23") (pin "P$1") (pinfunction "P$1_P$1") (pintype "bidirectional"))
    )
    (net (code "4") (name "L1_CHG") (class "Default")
      (node (ref "R15") (pin "2") (pinfunction "2_2") (pintype "passive"))
      (node (ref "U3") (pin "P$16") (pinfunction "RUN_P$16") (pintype "bidirectional"))
      (node (ref "V10") (pin "P$1") (pinfunction "P$1_P$1") (pintype "bidirectional"))
      (node (ref "V40") (pin "P$1") (pinfunction "P$1_P$1") (pintype "bidirectional"))
    )
    (net (code "5") (name "L1_CHGN") (class "Default")
      (node (ref "R17") (pin "1") (pinfunction "1_1") (pintype "passive"))
      (node (ref "U$6") (pin "P$8") (pinfunction "P04_P$8") (pintype "bidirectional"))
      (node (ref "U3") (pin "P$14") (pinfunction "~{CHRG}_P$14") (pintype "bidirectional"))
      (node (ref "V42") (pin "P$1") (pinfunction "P$1_P$1") (pintype "bidirectional"))
    )
    (net (code "6") (name "L1_DISG") (class "Default")
      (node (ref "U$1") (pin "P$3") (pinfunction "CNTRL_P$3") (pintype "bidirectional"))
      (node (ref "V34") (pin "P$1") (pinfunction "P$1_P$1") (pintype "bidirectional"))
      (node (ref "V46") (pin "P$1") (pinfunction "P$1_P$1") (pintype "bidirectional"))
    )
    (net (code "7") (name "L1_FAULTN") (class "Default")
      (node (ref "R18") (pin "1") (pinfunction "1_1") (pintype "passive"))
      (node (ref "U$6") (pin "P$9") (pinfunction "P05_P$9") (pintype "bidirectional"))
      (node (ref "U3") (pin "P$15") (pinfunction "~{FAULT}_P$15") (pintype "bidirectional"))
      (node (ref "V41") (pin "P$1") (pinfunction "P$1_P$1") (pintype "bidirectional"))
    )
    (net (code "8") (name "L1_REF") (class "Default")
      (node (ref "R33") (pin "1") (pinfunction "1_1") (pintype "passive"))
      (node (ref "R34") (pin "2") (pinfunction "2_2") (pintype "passive"))
      (node (ref "V25") (pin "P$1") (pinfunction "P$1_P$1") (pintype "bidirectional"))
      (node (ref "V44") (pin "P$1") (pinfunction "P$1_P$1") (pintype "bidirectional"))
    )
    (net (code "9") (name "L1_SNS") (class "Default")
      (node (ref "LI-ION1") (pin "MINUS") (pinfunction "MINUS_MINUS") (pintype "power_in"))
      (node (ref "R31") (pin "P$2") (pinfunction "2_P$2") (pintype "passive"))
      (node (ref "U$4") (pin "P$4") (pinfunction "VIN1_P$4") (pintype "bidirectional"))
      (node (ref "V43") (pin "P$1") (pinfunction "P$1_P$1") (pintype "bidirectional"))
    )
    (net (code "10") (name "L1_ST") (class "Default")
      (node (ref "R37") (pin "1") (pinfunction "1_1") (pintype "passive"))
      (node (ref "U$1") (pin "P$4") (pinfunction "STAT_P$4") (pintype "bidirectional"))
      (node (ref "U$6") (pin "P$5") (pinfunction "P01_P$5") (pintype "bidirectional"))
      (node (ref "V36") (pin "P$1") (pinfunction "P$1_P$1") (pintype "bidirectional"))
      (node (ref "V47") (pin "P$1") (pinfunction "P$1_P$1") (pintype "bidirectional"))
    )
    (net (code "11") (name "L1_TEMP") (class "Default")
      (node (ref "LION1TEMP") (pin "-") (pinfunction "-_-") (pintype "bidirectional"))
      (node (ref "V24") (pin "P$1") (pinfunction "P$1_P$1") (pintype "bidirectional"))
    )
    (net (code "12") (name "L2_CHG") (class "Default")
      (node (ref "R16") (pin "2") (pinfunction "2_2") (pintype "passive"))
      (node (ref "U4") (pin "P$16") (pinfunction "RUN_P$16") (pintype "bidirectional"))
      (node (ref "V33") (pin "P$1") (pinfunction "P$1_P$1") (pintype "bidirectional"))
    )
    (net (code "13") (name "L2_CHGN") (class "Default")
      (node (ref "R19") (pin "1") (pinfunction "1_1") (pintype "passive"))
      (node (ref "U$6") (pin "P$10") (pinfunction "P06_P$10") (pintype "bidirectional"))
      (node (ref "U4") (pin "P$14") (pinfunction "~{CHRG}_P$14") (pintype "bidirectional"))
    )
    (net (code "14") (name "L2_DISG") (class "Default")
      (node (ref "U$2") (pin "P$3") (pinfunction "CNTRL_P$3") (pintype "bidirectional"))
      (node (ref "V35") (pin "P$1") (pinfunction "P$1_P$1") (pintype "bidirectional"))
    )
    (net (code "15") (name "L2_FAULTN") (class "Default")
      (node (ref "R20") (pin "1") (pinfunction "1_1") (pintype "passive"))
      (node (ref "U$6") (pin "P$11") (pinfunction "P07_P$11") (pintype "bidirectional"))
      (node (ref "U4") (pin "P$15") (pinfunction "~{FAULT}_P$15") (pintype "bidirectional"))
    )
    (net (code "16") (name "L2_REF") (class "Default")
      (node (ref "R35") (pin "1") (pinfunction "1_1") (pintype "passive"))
      (node (ref "R36") (pin "2") (pinfunction "2_2") (pintype "passive"))
      (node (ref "V29") (pin "P$1") (pinfunction "P$1_P$1") (pintype "bidirectional"))
    )
    (net (code "17") (name "L2_SNS") (class "Default")
      (node (ref "LI-ION2") (pin "MINUS") (pinfunction "MINUS_MINUS") (pintype "power_in"))
      (node (ref "R32") (pin "P$2") (pinfunction "2_P$2") (pintype "passive"))
      (node (ref "U$4") (pin "P$3") (pinfunction "VIN0_P$3") (pintype "bidirectional"))
    )
    (net (code "18") (name "L2_ST") (class "Default")
      (node (ref "R38") (pin "1") (pinfunction "1_1") (pintype "passive"))
      (node (ref "U$2") (pin "P$4") (pinfunction "STAT_P$4") (pintype "bidirectional"))
      (node (ref "U$6") (pin "P$4") (pinfunction "P00_P$4") (pintype "bidirectional"))
      (node (ref "V38") (pin "P$1") (pinfunction "P$1_P$1") (pintype "bidirectional"))
    )
    (net (code "19") (name "L2_TEMP") (class "Default")
      (node (ref "LION2TEMP") (pin "-") (pinfunction "-_-") (pintype "bidirectional"))
      (node (ref "V32") (pin "P$1") (pinfunction "P$1_P$1") (pintype "bidirectional"))
    )
    (net (code "20") (name "LF1_REF") (class "Default")
      (node (ref "R49") (pin "2") (pinfunction "2_2") (pintype "passive"))
      (node (ref "R50") (pin "2") (pinfunction "2_2") (pintype "passive"))
      (node (ref "V58") (pin "P$1") (pinfunction "P$1_P$1") (pintype "bidirectional"))
    )
    (net (code "21") (name "LF1_TEMP") (class "Default")
      (node (ref "LIFE1TEMP") (pin "-") (pinfunction "-_-") (pintype "bidirectional"))
      (node (ref "V37") (pin "P$1") (pinfunction "P$1_P$1") (pintype "bidirectional"))
    )
    (net (code "22") (name "LF2_REF") (class "Default")
      (node (ref "R47") (pin "1") (pinfunction "1_1") (pintype "passive"))
      (node (ref "R48") (pin "2") (pinfunction "2_2") (pintype "passive"))
      (node (ref "V59") (pin "P$1") (pinfunction "P$1_P$1") (pintype "bidirectional"))
    )
    (net (code "23") (name "LF3_REF") (class "Default")
      (node (ref "R67") (pin "2") (pinfunction "2_2") (pintype "passive"))
      (node (ref "R68") (pin "2") (pinfunction "2_2") (pintype "passive"))
      (node (ref "V62") (pin "P$1") (pinfunction "P$1_P$1") (pintype "bidirectional"))
    )
    (net (code "24") (name "LF3_TEMP") (class "Default")
      (node (ref "LIFE3TEMP") (pin "-") (pinfunction "-_-") (pintype "bidirectional"))
      (node (ref "V50") (pin "P$1") (pinfunction "P$1_P$1") (pintype "bidirectional"))
    )
    (net (code "25") (name "LF4_REF") (class "Default")
      (node (ref "R65") (pin "1") (pinfunction "1_1") (pintype "passive"))
      (node (ref "R66") (pin "2") (pinfunction "2_2") (pintype "passive"))
      (node (ref "V61") (pin "P$1") (pinfunction "P$1_P$1") (pintype "bidirectional"))
    )
    (net (code "26") (name "LF_B1") (class "Default")
      (node (ref "C23") (pin "1") (pinfunction "P$1_1") (pintype "passive"))
      (node (ref "SW1") (pin "P$5") (pinfunction "OUT_P$5") (pintype "power_in"))
      (node (ref "SW1") (pin "P$6") (pinfunction "OUT_P$6") (pintype "power_in"))
      (node (ref "SW1") (pin "P$7") (pinfunction "OUT_P$7") (pintype "power_in"))
      (node (ref "V21") (pin "P$1") (pinfunction "P$1_P$1") (pintype "bidirectional"))
      (node (ref "V26") (pin "P$1") (pinfunction "P$1_P$1") (pintype "bidirectional"))
    )
    (net (code "27") (name "LF_B1_BT") (class "Default")
      (node (ref "R57") (pin "2") (pinfunction "2_2") (pintype "passive"))
      (node (ref "U$3") (pin "P$4") (pinfunction "G2_P$4") (pintype "bidirectional"))
      (node (ref "U$6") (pin "P$13") (pinfunction "P10_P$13") (pintype "bidirectional"))
    )
    (net (code "28") (name "LF_B1_CHG") (class "Default")
      (node (ref "R44") (pin "2") (pinfunction "2_2") (pintype "passive"))
      (node (ref "U5") (pin "P$16") (pinfunction "RUN_P$16") (pintype "bidirectional"))
      (node (ref "V15") (pin "P$1") (pinfunction "P$1_P$1") (pintype "bidirectional"))
    )
    (net (code "29") (name "LF_B1_CHGN") (class "Default")
      (node (ref "R42") (pin "1") (pinfunction "1_1") (pintype "passive"))
      (node (ref "U$6") (pin "P$19") (pinfunction "P16_P$19") (pintype "bidirectional"))
      (node (ref "U5") (pin "P$14") (pinfunction "~{CHRG}_P$14") (pintype "bidirectional"))
      (node (ref "V18") (pin "P$1") (pinfunction "P$1_P$1") (pintype "bidirectional"))
    )
    (net (code "30") (name "LF_B1_FAULTN") (class "Default")
      (node (ref "R43") (pin "1") (pinfunction "1_1") (pintype "passive"))
      (node (ref "U$6") (pin "P$20") (pinfunction "P17_P$20") (pintype "bidirectional"))
      (node (ref "U5") (pin "P$15") (pinfunction "~{FAULT}_P$15") (pintype "bidirectional"))
      (node (ref "V19") (pin "P$1") (pinfunction "P$1_P$1") (pintype "bidirectional"))
    )
    (net (code "31") (name "LF_B1_OSNS") (class "Default")
      (node (ref "C24") (pin "1") (pinfunction "P$1_1") (pintype "passive"))
      (node (ref "R79") (pin "1") (pinfunction "1_1") (pintype "passive"))
      (node (ref "V31") (pin "P$1") (pinfunction "P$1_P$1") (pintype "bidirectional"))
    )
    (net (code "32") (name "LF_B1_OUTEN") (class "Default")
      (node (ref "R78") (pin "1") (pinfunction "1_1") (pintype "passive"))
      (node (ref "V20") (pin "P$1") (pinfunction "P$1_P$1") (pintype "bidirectional"))
    )
    (net (code "34") (name "LF_B1_TT") (class "Default")
      (node (ref "R56") (pin "2") (pinfunction "2_2") (pintype "passive"))
      (node (ref "U$3") (pin "P$2") (pinfunction "G1_P$2") (pintype "bidirectional"))
      (node (ref "U$6") (pin "P$14") (pinfunction "P11_P$14") (pintype "bidirectional"))
    )
    (net (code "36") (name "LF_B2_BT") (class "Default")
      (node (ref "R75") (pin "2") (pinfunction "2_2") (pintype "passive"))
      (node (ref "U$5") (pin "P$4") (pinfunction "G2_P$4") (pintype "bidirectional"))
      (node (ref "U$6") (pin "P$16") (pinfunction "P13_P$16") (pintype "bidirectional"))
    )
    (net (code "37") (name "LF_B2_CHG") (class "Default")
      (node (ref "R62") (pin "2") (pinfunction "2_2") (pintype "passive"))
      (node (ref "U6") (pin "P$16") (pinfunction "RUN_P$16") (pintype "bidirectional"))
      (node (ref "V57") (pin "P$1") (pinfunction "P$1_P$1") (pintype "bidirectional"))
    )
    (net (code "38") (name "LF_B2_CHGN") (class "Default")
      (node (ref "R60") (pin "1") (pinfunction "1_1") (pintype "passive"))
      (node (ref "U$6") (pin "P$17") (pinfunction "P14_P$17") (pintype "bidirectional"))
      (node (ref "U6") (pin "P$14") (pinfunction "~{CHRG}_P$14") (pintype "bidirectional"))
    )
    (net (code "39") (name "LF_B2_FAULTN") (class "Default")
      (node (ref "R61") (pin "1") (pinfunction "1_1") (pintype "passive"))
      (node (ref "U$6") (pin "P$18") (pinfunction "P15_P$18") (pintype "bidirectional"))
      (node (ref "U6") (pin "P$15") (pinfunction "~{FAULT}_P$15") (pintype "bidirectional"))
    )
    (net (code "40") (name "LF_B2_OSNS") (class "Default")
      (node (ref "C27") (pin "1") (pinfunction "P$1_1") (pintype "passive"))
      (node (ref "R82") (pin "1") (pinfunction "1_1") (pintype "passive"))
      (node (ref "V63") (pin "P$1") (pinfunction "P$1_P$1") (pintype "bidirectional"))
    )
    (net (code "41") (name "LF_B2_OUTEN") (class "Default")
      (node (ref "R81") (pin "1") (pinfunction "1_1") (pintype "passive"))
      (node (ref "V56") (pin "P$1") (pinfunction "P$1_P$1") (pintype "bidirectional"))
    )
    (net (code "42") (name "LF_B2_SNS") (class "Default")
      (node (ref "LIFEPO4") (pin "MINUS") (pinfunction "MINUS_MINUS") (pintype "power_in"))
      (node (ref "R59") (pin "P$2") (pinfunction "2_P$2") (pintype "passive"))
      (node (ref "V60") (pin "P$1") (pinfunction "P$1_P$1") (pintype "bidirectional"))
    )
    (net (code "43") (name "LF_B2_TT") (class "Default")
      (node (ref "R74") (pin "2") (pinfunction "2_2") (pintype "passive"))
      (node (ref "U$5") (pin "P$2") (pinfunction "G1_P$2") (pintype "bidirectional"))
      (node (ref "U$6") (pin "P$15") (pinfunction "P12_P$15") (pintype "bidirectional"))
    )
    (net (code "44") (name "LIFE1") (class "Default")
      (node (ref "C18") (pin "1") (pinfunction "P$1_1") (pintype "passive"))
      (node (ref "LIFEPO1") (pin "PLUS") (pinfunction "PLUS_PLUS") (pintype "power_in"))
      (node (ref "R49") (pin "1") (pinfunction "1_1") (pintype "passive"))
      (node (ref "R53") (pin "2") (pinfunction "2_2") (pintype "passive"))
      (node (ref "R54") (pin "P$2") (pinfunction "2_P$2") (pintype "passive"))
      (node (ref "SW1") (pin "PAD") (pinfunction "VB_PAD") (pintype "power_in"))
      (node (ref "U5") (pin "P$9") (pinfunction "BAT_P$9") (pintype "bidirectional"))
      (node (ref "V17") (pin "P$1") (pinfunction "P$1_P$1") (pintype "bidirectional"))
    )
    (net (code "45") (name "LIFE3") (class "Default")
      (node (ref "C22") (pin "1") (pinfunction "P$1_1") (pintype "passive"))
      (node (ref "LIFEPO3") (pin "PLUS") (pinfunction "PLUS_PLUS") (pintype "power_in"))
      (node (ref "R67") (pin "1") (pinfunction "1_1") (pintype "passive"))
      (node (ref "R71") (pin "2") (pinfunction "2_2") (pintype "passive"))
      (node (ref "R72") (pin "P$2") (pinfunction "2_P$2") (pintype "passive"))
      (node (ref "SW2") (pin "PAD") (pinfunction "VB_PAD") (pintype "power_in"))
      (node (ref "U6") (pin "P$9") (pinfunction "BAT_P$9") (pintype "bidirectional"))
    )
    (net (code "46") (name "LIFEB1SNS") (class "Default")
      (node (ref "LIFEPO2") (pin "MINUS") (pinfunction "MINUS_MINUS") (pintype "power_in"))
      (node (ref "R41") (pin "P$2") (pinfunction "2_P$2") (pintype "passive"))
      (node (ref "V14") (pin "P$1") (pinfunction "P$1_P$1") (pintype "bidirectional"))
    )
    (net (code "47") (name "LIFE_B2") (class "Default")
      (node (ref "C26") (pin "1") (pinfunction "P$1_1") (pintype "passive"))
      (node (ref "SW2") (pin "P$5") (pinfunction "OUT_P$5") (pintype "power_in"))
      (node (ref "SW2") (pin "P$6") (pinfunction "OUT_P$6") (pintype "power_in"))
      (node (ref "SW2") (pin "P$7") (pinfunction "OUT_P$7") (pintype "power_in"))
      (node (ref "V27") (pin "P$1") (pinfunction "P$1_P$1") (pintype "bidirectional"))
      (node (ref "V28") (pin "P$1") (pinfunction "P$1_P$1") (pintype "bidirectional"))
    )
    (net (code "48") (name "LION1") (class "Default")
      (node (ref "C13") (pin "2") (pinfunction "P$2_2") (pintype "passive"))
      (node (ref "C8") (pin "1") (pinfunction "P$1_1") (pintype "passive"))
      (node (ref "LI-ION1") (pin "PLUS") (pinfunction "PLUS_PLUS") (pintype "power_in"))
      (node (ref "R21") (pin "2") (pinfunction "2_2") (pintype "passive"))
      (node (ref "R33") (pin "2") (pinfunction "2_2") (pintype "passive"))
      (node (ref "U$1") (pin "P$1") (pinfunction "IN_P$1") (pintype "bidirectional"))
      (node (ref "U3") (pin "P$9") (pinfunction "BAT_P$9") (pintype "bidirectional"))
      (node (ref "V45") (pin "P$1") (pinfunction "P$1_P$1") (pintype "bidirectional"))
    )
    (net (code "49") (name "LION2") (class "Default")
      (node (ref "C14") (pin "2") (pinfunction "P$2_2") (pintype "passive"))
      (node (ref "C9") (pin "1") (pinfunction "P$1_1") (pintype "passive"))
      (node (ref "LI-ION2") (pin "PLUS") (pinfunction "PLUS_PLUS") (pintype "power_in"))
      (node (ref "R24") (pin "2") (pinfunction "2_2") (pintype "passive"))
      (node (ref "R35") (pin "2") (pinfunction "2_2") (pintype "passive"))
      (node (ref "U$2") (pin "P$1") (pinfunction "IN_P$1") (pintype "bidirectional"))
      (node (ref "U4") (pin "P$9") (pinfunction "BAT_P$9") (pintype "bidirectional"))
    )
    (net (code "50") (name "L_OUT") (class "Default")
      (node (ref "C11") (pin "1") (pinfunction "P$1_1") (pintype "passive"))
      (node (ref "C12") (pin "1") (pinfunction "P$1_1") (pintype "passive"))
      (node (ref "R37") (pin "2") (pinfunction "2_2") (pintype "passive"))
      (node (ref "R38") (pin "2") (pinfunction "2_2") (pintype "passive"))
      (node (ref "R39") (pin "2") (pinfunction "2_2") (pintype "passive"))
      (node (ref "U$1") (pin "P$5") (pinfunction "OUT_P$5") (pintype "bidirectional"))
      (node (ref "U$2") (pin "P$5") (pinfunction "OUT_P$5") (pintype "bidirectional"))
      (node (ref "V30") (pin "P$1") (pinfunction "P$1_P$1") (pintype "bidirectional"))
      (node (ref "V48") (pin "P$1") (pinfunction "P$1_P$1") (pintype "bidirectional"))
      (node (ref "V54") (pin "P$1") (pinfunction "P$1_P$1") (pintype "bidirectional"))
    )
    (net (code "51") (name "L_REF") (class "Default")
      (node (ref "R39") (pin "1") (pinfunction "1_1") (pintype "passive"))
      (node (ref "R40") (pin "2") (pinfunction "2_2") (pintype "passive"))
      (node (ref "U$4") (pin "P$5") (pinfunction "VIN2_P$5") (pintype "bidirectional"))
    )
    (net (code "52") (name "Net-(C1-P$1)") (class "Default")
      (node (ref "C1") (pin "1") (pinfunction "P$1_1") (pintype "passive"))
      (node (ref "M1") (pin "P$5") (pinfunction "D_P$5") (pintype "bidirectional"))
      (node (ref "M1") (pin "P$6") (pinfunction "D_P$6") (pintype "bidirectional"))
      (node (ref "M1") (pin "P$7") (pinfunction "D_P$7") (pintype "bidirectional"))
      (node (ref "M1") (pin "P$8") (pinfunction "D_P$8") (pintype "bidirectional"))
      (node (ref "R2") (pin "2") (pinfunction "2_2") (pintype "passive"))
      (node (ref "U1") (pin "P$1") (pinfunction "VIN_P$1") (pintype "bidirectional"))
    )
    (net (code "53") (name "Net-(C2-P$1)") (class "Default")
      (node (ref "C2") (pin "1") (pinfunction "P$1_1") (pintype "passive"))
      (node (ref "M1") (pin "P$1") (pinfunction "S_P$1") (pintype "bidirectional"))
      (node (ref "M1") (pin "P$2") (pinfunction "S_P$2") (pintype "bidirectional"))
      (node (ref "M1") (pin "P$3") (pinfunction "S_P$3") (pintype "bidirectional"))
      (node (ref "R4") (pin "1") (pinfunction "1_1") (pintype "passive"))
      (node (ref "U1") (pin "P$6") (pinfunction "SNS_P$6") (pintype "bidirectional"))
    )
    (net (code "54") (name "Net-(C4-P$1)") (class "Default")
      (node (ref "C4") (pin "1") (pinfunction "P$1_1") (pintype "passive"))
      (node (ref "U3") (pin "P$2") (pinfunction "BOOST_P$2") (pintype "bidirectional"))
    )
    (net (code "55") (name "Net-(C4-P$2)") (class "Default")
      (node (ref "C4") (pin "2") (pinfunction "P$2_2") (pintype "passive"))
      (node (ref "L1") (pin "P$1") (pinfunction "P$1_P$1") (pintype "passive"))
      (node (ref "U3") (pin "P$4") (pinfunction "SW_P$4") (pintype "bidirectional"))
    )
    (net (code "56") (name "Net-(C5-P$1)") (class "Default")
      (node (ref "C5") (pin "1") (pinfunction "P$1_1") (pintype "passive"))
      (node (ref "U4") (pin "P$2") (pinfunction "BOOST_P$2") (pintype "bidirectional"))
    )
    (net (code "57") (name "Net-(C5-P$2)") (class "Default")
      (node (ref "C5") (pin "2") (pinfunction "P$2_2") (pintype "passive"))
      (node (ref "L2") (pin "P$1") (pinfunction "P$1_P$1") (pintype "passive"))
      (node (ref "U4") (pin "P$4") (pinfunction "SW_P$4") (pintype "bidirectional"))
    )
    (net (code "58") (name "Net-(C6-P$1)") (class "Default")
      (node (ref "C6") (pin "1") (pinfunction "P$1_1") (pintype "passive"))
      (node (ref "U3") (pin "P$1") (pinfunction "INTVCC_P$1") (pintype "bidirectional"))
    )
    (net (code "59") (name "Net-(C7-P$1)") (class "Default")
      (node (ref "C7") (pin "1") (pinfunction "P$1_1") (pintype "passive"))
      (node (ref "U4") (pin "P$1") (pinfunction "INTVCC_P$1") (pintype "bidirectional"))
    )
    (net (code "60") (name "Net-(C15-P$2)") (class "Default")
      (node (ref "C15") (pin "2") (pinfunction "P$2_2") (pintype "passive"))
      (node (ref "U5") (pin "P$1") (pinfunction "INTVCC_P$1") (pintype "bidirectional"))
    )
    (net (code "61") (name "Net-(C16-P$1)") (class "Default")
      (node (ref "C16") (pin "1") (pinfunction "P$1_1") (pintype "passive"))
      (node (ref "L3") (pin "P$2") (pinfunction "P$2_P$2") (pintype "passive"))
      (node (ref "U5") (pin "P$4") (pinfunction "SW_P$4") (pintype "bidirectional"))
    )
    (net (code "62") (name "Net-(C16-P$2)") (class "Default")
      (node (ref "C16") (pin "2") (pinfunction "P$2_2") (pintype "passive"))
      (node (ref "U5") (pin "P$2") (pinfunction "BOOST_P$2") (pintype "bidirectional"))
    )
    (net (code "63") (name "Net-(C19-P$2)") (class "Default")
      (node (ref "C19") (pin "2") (pinfunction "P$2_2") (pintype "passive"))
      (node (ref "U6") (pin "P$1") (pinfunction "INTVCC_P$1") (pintype "bidirectional"))
    )
    (net (code "64") (name "Net-(C20-P$1)") (class "Default")
      (node (ref "C20") (pin "1") (pinfunction "P$1_1") (pintype "passive"))
      (node (ref "L4") (pin "P$2") (pinfunction "P$2_P$2") (pintype "passive"))
      (node (ref "U6") (pin "P$4") (pinfunction "SW_P$4") (pintype "bidirectional"))
    )
    (net (code "65") (name "Net-(C20-P$2)") (class "Default")
      (node (ref "C20") (pin "2") (pinfunction "P$2_2") (pintype "passive"))
      (node (ref "U6") (pin "P$2") (pinfunction "BOOST_P$2") (pintype "bidirectional"))
    )
    (net (code "66") (name "Net-(C25-P$2)") (class "Default")
      (node (ref "C25") (pin "2") (pinfunction "P$2_2") (pintype "passive"))
      (node (ref "R77") (pin "2") (pinfunction "2_2") (pintype "passive"))
      (node (ref "R78") (pin "2") (pinfunction "2_2") (pintype "passive"))
      (node (ref "SW1") (pin "P$2") (pinfunction "CNTRL_P$2") (pintype "input"))
    )
    (net (code "67") (name "Net-(C28-P$2)") (class "Default")
      (node (ref "C28") (pin "2") (pinfunction "P$2_2") (pintype "passive"))
      (node (ref "R80") (pin "2") (pinfunction "2_2") (pintype "passive"))
      (node (ref "R81") (pin "2") (pinfunction "2_2") (pintype "passive"))
      (node (ref "SW2") (pin "P$2") (pinfunction "CNTRL_P$2") (pintype "input"))
    )
    (net (code "68") (name "Net-(D7-PadA)") (class "Default")
      (node (ref "D7") (pin "A") (pinfunction "A_A") (pintype "bidirectional"))
      (node (ref "R1") (pin "2") (pinfunction "2_2") (pintype "passive"))
    )
    (net (code "69") (name "Net-(D7-PadC)") (class "Default")
      (node (ref "D7") (pin "C") (pinfunction "C_C") (pintype "bidirectional"))
      (node (ref "R3") (pin "1") (pinfunction "1_1") (pintype "passive"))
    )
    (net (code "70") (name "Net-(M1-G)") (class "Default")
      (node (ref "M1") (pin "P$4") (pinfunction "G_P$4") (pintype "bidirectional"))
      (node (ref "U1") (pin "P$5") (pinfunction "GATE_P$5") (pintype "bidirectional"))
    )
    (net (code "71") (name "Net-(R54-1)") (class "Default")
      (node (ref "R54") (pin "P$1") (pinfunction "1_P$1") (pintype "passive"))
      (node (ref "U$3") (pin "P$7") (pinfunction "D1_P$7") (pintype "bidirectional"))
      (node (ref "U$3") (pin "P$8") (pinfunction "D1_P$8") (pintype "bidirectional"))
    )
    (net (code "72") (name "Net-(R55-1)") (class "Default")
      (node (ref "LIFEPO1") (pin "MINUS") (pinfunction "MINUS_MINUS") (pintype "power_in"))
      (node (ref "LIFEPO2") (pin "PLUS") (pinfunction "PLUS_PLUS") (pintype "power_in"))
      (node (ref "R47") (pin "2") (pinfunction "2_2") (pintype "passive"))
      (node (ref "R55") (pin "P$1") (pinfunction "1_P$1") (pintype "passive"))
      (node (ref "U$3") (pin "P$1") (pinfunction "S1_P$1") (pintype "bidirectional"))
      (node (ref "V16") (pin "P$1") (pinfunction "P$1_P$1") (pintype "bidirectional"))
    )
    (net (code "73") (name "Net-(R55-2)") (class "Default")
      (node (ref "R55") (pin "P$2") (pinfunction "2_P$2") (pintype "passive"))
      (node (ref "U$3") (pin "P$5") (pinfunction "D2_P$5") (pintype "bidirectional"))
      (node (ref "U$3") (pin "P$6") (pinfunction "D2_P$6") (pintype "bidirectional"))
    )
    (net (code "74") (name "Net-(R72-1)") (class "Default")
      (node (ref "R72") (pin "P$1") (pinfunction "1_P$1") (pintype "passive"))
      (node (ref "U$5") (pin "P$7") (pinfunction "D1_P$7") (pintype "bidirectional"))
      (node (ref "U$5") (pin "P$8") (pinfunction "D1_P$8") (pintype "bidirectional"))
    )
    (net (code "75") (name "Net-(R73-1)") (class "Default")
      (node (ref "LIFEPO3") (pin "MINUS") (pinfunction "MINUS_MINUS") (pintype "power_in"))
      (node (ref "LIFEPO4") (pin "PLUS") (pinfunction "PLUS_PLUS") (pintype "power_in"))
      (node (ref "R65") (pin "2") (pinfunction "2_2") (pintype "passive"))
      (node (ref "R73") (pin "P$1") (pinfunction "1_P$1") (pintype "passive"))
      (node (ref "U$5") (pin "P$1") (pinfunction "S1_P$1") (pintype "bidirectional"))
    )
    (net (code "76") (name "Net-(R73-2)") (class "Default")
      (node (ref "R73") (pin "P$2") (pinfunction "2_P$2") (pintype "passive"))
      (node (ref "U$5") (pin "P$5") (pinfunction "D2_P$5") (pintype "bidirectional"))
      (node (ref "U$5") (pin "P$6") (pinfunction "D2_P$6") (pintype "bidirectional"))
    )
    (net (code "77") (name "Net-(SW1-ISNS)") (class "Default")
      (node (ref "R58") (pin "2") (pinfunction "2_2") (pintype "passive"))
      (node (ref "R79") (pin "2") (pinfunction "2_2") (pintype "passive"))
      (node (ref "SW1") (pin "P$3") (pinfunction "ISNS_P$3") (pintype "output"))
    )
    (net (code "78") (name "Net-(SW2-ISNS)") (class "Default")
      (node (ref "R76") (pin "2") (pinfunction "2_2") (pintype "passive"))
      (node (ref "R82") (pin "2") (pinfunction "2_2") (pintype "passive"))
      (node (ref "SW2") (pin "P$3") (pinfunction "ISNS_P$3") (pintype "output"))
    )
    (net (code "79") (name "Net-(U3-CHGSNS)") (class "Default")
      (node (ref "L1") (pin "P$2") (pinfunction "P$2_P$2") (pintype "passive"))
      (node (ref "U3") (pin "P$8") (pinfunction "CHGSNS_P$8") (pintype "bidirectional"))
    )
    (net (code "80") (name "Net-(U3-FB)") (class "Default")
      (node (ref "R21") (pin "1") (pinfunction "1_1") (pintype "passive"))
      (node (ref "R22") (pin "2") (pinfunction "2_2") (pintype "passive"))
      (node (ref "U3") (pin "P$10") (pinfunction "FB_P$10") (pintype "bidirectional"))
    )
    (net (code "81") (name "Net-(U3-FBG)") (class "Default")
      (node (ref "R22") (pin "1") (pinfunction "1_1") (pintype "passive"))
      (node (ref "U3") (pin "P$11") (pinfunction "FBG_P$11") (pintype "bidirectional"))
    )
    (net (code "82") (name "Net-(U3-MPPT)") (class "Default")
      (node (ref "R27") (pin "1") (pinfunction "1_1") (pintype "passive"))
      (node (ref "R28") (pin "2") (pinfunction "2_2") (pintype "passive"))
      (node (ref "U3") (pin "P$6") (pinfunction "MPPT_P$6") (pintype "bidirectional"))
    )
    (net (code "83") (name "Net-(U3-PROG)") (class "Default")
      (node (ref "R25") (pin "2") (pinfunction "2_2") (pintype "passive"))
      (node (ref "U3") (pin "P$13") (pinfunction "PROG_P$13") (pintype "bidirectional"))
    )
    (net (code "84") (name "Net-(U4-CHGSNS)") (class "Default")
      (node (ref "L2") (pin "P$2") (pinfunction "P$2_P$2") (pintype "passive"))
      (node (ref "U4") (pin "P$8") (pinfunction "CHGSNS_P$8") (pintype "bidirectional"))
    )
    (net (code "85") (name "Net-(U4-FB)") (class "Default")
      (node (ref "R23") (pin "2") (pinfunction "2_2") (pintype "passive"))
      (node (ref "R24") (pin "1") (pinfunction "1_1") (pintype "passive"))
      (node (ref "U4") (pin "P$10") (pinfunction "FB_P$10") (pintype "bidirectional"))
    )
    (net (code "86") (name "Net-(U4-FBG)") (class "Default")
      (node (ref "R23") (pin "1") (pinfunction "1_1") (pintype "passive"))
      (node (ref "U4") (pin "P$11") (pinfunction "FBG_P$11") (pintype "bidirectional"))
    )
    (net (code "87") (name "Net-(U4-MPPT)") (class "Default")
      (node (ref "R29") (pin "2") (pinfunction "2_2") (pintype "passive"))
      (node (ref "R30") (pin "1") (pinfunction "1_1") (pintype "passive"))
      (node (ref "U4") (pin "P$6") (pinfunction "MPPT_P$6") (pintype "bidirectional"))
    )
    (net (code "88") (name "Net-(U4-PROG)") (class "Default")
      (node (ref "R26") (pin "2") (pinfunction "2_2") (pintype "passive"))
      (node (ref "U4") (pin "P$13") (pinfunction "PROG_P$13") (pintype "bidirectional"))
    )
    (net (code "89") (name "Net-(U5-CHGSNS)") (class "Default")
      (node (ref "L3") (pin "P$1") (pinfunction "P$1_P$1") (pintype "passive"))
      (node (ref "U5") (pin "P$8") (pinfunction "CHGSNS_P$8") (pintype "bidirectional"))
    )
    (net (code "90") (name "Net-(U5-FB)") (class "Default")
      (node (ref "R52") (pin "2") (pinfunction "2_2") (pintype "passive"))
      (node (ref "R53") (pin "1") (pinfunction "1_1") (pintype "passive"))
      (node (ref "U5") (pin "P$10") (pinfunction "FB_P$10") (pintype "bidirectional"))
    )
    (net (code "91") (name "Net-(U5-FBG)") (class "Default")
      (node (ref "R52") (pin "1") (pinfunction "1_1") (pintype "passive"))
      (node (ref "U5") (pin "P$11") (pinfunction "FBG_P$11") (pintype "bidirectional"))
    )
    (net (code "92") (name "Net-(U5-MPPT)") (class "Default")
      (node (ref "R45") (pin "1") (pinfunction "1_1") (pintype "passive"))
      (node (ref "R46") (pin "2") (pinfunction "2_2") (pintype "passive"))
      (node (ref "U5") (pin "P$6") (pinfunction "MPPT_P$6") (pintype "bidirectional"))
    )
    (net (code "93") (name "Net-(U5-PROG)") (class "Default")
      (node (ref "R51") (pin "1") (pinfunction "1_1") (pintype "passive"))
      (node (ref "U5") (pin "P$13") (pinfunction "PROG_P$13") (pintype "bidirectional"))
    )
    (net (code "94") (name "Net-(U6-CHGSNS)") (class "Default")
      (node (ref "L4") (pin "P$1") (pinfunction "P$1_P$1") (pintype "passive"))
      (node (ref "U6") (pin "P$8") (pinfunction "CHGSNS_P$8") (pintype "bidirectional"))
    )
    (net (code "95") (name "Net-(U6-FB)") (class "Default")
      (node (ref "R70") (pin "2") (pinfunction "2_2") (pintype "passive"))
      (node (ref "R71") (pin "1") (pinfunction "1_1") (pintype "passive"))
      (node (ref "U6") (pin "P$10") (pinfunction "FB_P$10") (pintype "bidirectional"))
    )
    (net (code "96") (name "Net-(U6-FBG)") (class "Default")
      (node (ref "R70") (pin "1") (pinfunction "1_1") (pintype "passive"))
      (node (ref "U6") (pin "P$11") (pinfunction "FBG_P$11") (pintype "bidirectional"))
    )
    (net (code "97") (name "Net-(U6-MPPT)") (class "Default")
      (node (ref "R63") (pin "1") (pinfunction "1_1") (pintype "passive"))
      (node (ref "R64") (pin "2") (pinfunction "2_2") (pintype "passive"))
      (node (ref "U6") (pin "P$6") (pinfunction "MPPT_P$6") (pintype "bidirectional"))
    )
    (net (code "98") (name "Net-(U6-PROG)") (class "Default")
      (node (ref "R69") (pin "1") (pinfunction "1_1") (pintype "passive"))
      (node (ref "U6") (pin "P$13") (pinfunction "PROG_P$13") (pintype "bidirectional"))
    )
    (net (code "99") (name "PANELREF") (class "Default")
      (node (ref "R13") (pin "1") (pinfunction "1_1") (pintype "passive"))
      (node (ref "R14") (pin "2") (pinfunction "2_2") (pintype "passive"))
      (node (ref "U$4") (pin "P$6") (pinfunction "VIN3/REF_P$6") (pintype "bidirectional"))
    )
    (net (code "100") (name "SCL") (class "Default")
      (node (ref "R85") (pin "1") (pinfunction "1_1") (pintype "passive"))
      (node (ref "U$4") (pin "P$1") (pinfunction "SCL_P$1") (pintype "bidirectional"))
      (node (ref "U$6") (pin "P$22") (pinfunction "SCL_P$22") (pintype "bidirectional"))
      (node (ref "V52") (pin "P$1") (pinfunction "P$1_P$1") (pintype "bidirectional"))
    )
    (net (code "101") (name "SDA") (class "Default")
      (node (ref "R86") (pin "1") (pinfunction "1_1") (pintype "passive"))
      (node (ref "U$4") (pin "P$2") (pinfunction "SDA_P$2") (pintype "bidirectional"))
      (node (ref "U$6") (pin "P$23") (pinfunction "SDA_P$23") (pintype "bidirectional"))
      (node (ref "V53") (pin "P$1") (pinfunction "P$1_P$1") (pintype "bidirectional"))
    )
    (net (code "102") (name "SPF_ST") (class "Default")
      (node (ref "R83") (pin "1") (pinfunction "1_1") (pintype "passive"))
      (node (ref "U$6") (pin "P$6") (pinfunction "P02_P$6") (pintype "bidirectional"))
      (node (ref "U1") (pin "P$4") (pinfunction "STAT_P$4") (pintype "bidirectional"))
    )
    (net (code "103") (name "SP_C") (class "Default")
      (node (ref "D1") (pin "C") (pinfunction "C_C") (pintype "bidirectional"))
      (node (ref "D2") (pin "C") (pinfunction "C_C") (pintype "bidirectional"))
      (node (ref "D3") (pin "C") (pinfunction "C_C") (pintype "bidirectional"))
      (node (ref "D4") (pin "C") (pinfunction "C_C") (pintype "bidirectional"))
      (node (ref "D5") (pin "C") (pinfunction "C_C") (pintype "bidirectional"))
      (node (ref "R1") (pin "1") (pinfunction "1_1") (pintype "passive"))
      (node (ref "R10") (pin "2") (pinfunction "2_2") (pintype "passive"))
      (node (ref "R2") (pin "1") (pinfunction "1_1") (pintype "passive"))
      (node (ref "R5") (pin "1") (pinfunction "1_1") (pintype "passive"))
      (node (ref "R6") (pin "2") (pinfunction "2_2") (pintype "passive"))
      (node (ref "R7") (pin "2") (pinfunction "2_2") (pintype "passive"))
      (node (ref "R8") (pin "2") (pinfunction "2_2") (pintype "passive"))
      (node (ref "R9") (pin "2") (pinfunction "2_2") (pintype "passive"))
    )
    (net (code "104") (name "SP_C_O") (class "Default")
      (node (ref "R11") (pin "1") (pinfunction "1_1") (pintype "passive"))
      (node (ref "R12") (pin "1") (pinfunction "1_1") (pintype "passive"))
      (node (ref "R3") (pin "2") (pinfunction "2_2") (pintype "passive"))
      (node (ref "R4") (pin "2") (pinfunction "2_2") (pintype "passive"))
      (node (ref "R5") (pin "2") (pinfunction "2_2") (pintype "passive"))
      (node (ref "V7") (pin "P$1") (pinfunction "P$1_P$1") (pintype "bidirectional"))
    )
    (net (code "105") (name "SP_OUT") (class "Default")
      (node (ref "C10") (pin "1") (pinfunction "P$1_1") (pintype "passive"))
      (node (ref "C17") (pin "2") (pinfunction "P$2_2") (pintype "passive"))
      (node (ref "C21") (pin "2") (pinfunction "P$2_2") (pintype "passive"))
      (node (ref "C3") (pin "1") (pinfunction "P$1_1") (pintype "passive"))
      (node (ref "D6") (pin "C") (pinfunction "C_C") (pintype "bidirectional"))
      (node (ref "R11") (pin "2") (pinfunction "2_2") (pintype "passive"))
      (node (ref "R12") (pin "2") (pinfunction "2_2") (pintype "passive"))
      (node (ref "R13") (pin "2") (pinfunction "2_2") (pintype "passive"))
      (node (ref "R15") (pin "1") (pinfunction "1_1") (pintype "passive"))
      (node (ref "R16") (pin "1") (pinfunction "1_1") (pintype "passive"))
      (node (ref "R27") (pin "2") (pinfunction "2_2") (pintype "passive"))
      (node (ref "R30") (pin "2") (pinfunction "2_2") (pintype "passive"))
      (node (ref "R45") (pin "2") (pinfunction "2_2") (pintype "passive"))
      (node (ref "R63") (pin "2") (pinfunction "2_2") (pintype "passive"))
      (node (ref "U3") (pin "P$3") (pinfunction "IN_P$3") (pintype "bidirectional"))
      (node (ref "U4") (pin "P$3") (pinfunction "IN_P$3") (pintype "bidirectional"))
      (node (ref "U5") (pin "P$3") (pinfunction "IN_P$3") (pintype "bidirectional"))
      (node (ref "U6") (pin "P$3") (pinfunction "IN_P$3") (pintype "bidirectional"))
      (node (ref "V8") (pin "P$1") (pinfunction "P$1_P$1") (pintype "bidirectional"))
    )
    (net (code "106") (name "UMB_CHG") (class "Default")
      (node (ref "D6") (pin "A") (pinfunction "A_A") (pintype "bidirectional"))
      (node (ref "V1") (pin "P$1") (pinfunction "P$1_P$1") (pintype "bidirectional"))
      (node (ref "V39") (pin "P$1") (pinfunction "P$1_P$1") (pintype "bidirectional"))
    )
    (net (code "107") (name "X_N") (class "Default")
      (node (ref "D2") (pin "A") (pinfunction "A_A") (pintype "bidirectional"))
      (node (ref "R7") (pin "1") (pinfunction "1_1") (pintype "passive"))
      (node (ref "V3") (pin "P$1") (pinfunction "P$1_P$1") (pintype "bidirectional"))
    )
    (net (code "108") (name "X_P") (class "Default")
      (node (ref "D1") (pin "A") (pinfunction "A_A") (pintype "bidirectional"))
      (node (ref "R6") (pin "1") (pinfunction "1_1") (pintype "passive"))
      (node (ref "V2") (pin "P$1") (pinfunction "P$1_P$1") (pintype "bidirectional"))
      (node (ref "V49") (pin "P$1") (pinfunction "P$1_P$1") (pintype "bidirectional"))
    )
    (net (code "109") (name "Y_N") (class "Default")
      (node (ref "D5") (pin "A") (pinfunction "A_A") (pintype "bidirectional"))
      (node (ref "R10") (pin "1") (pinfunction "1_1") (pintype "passive"))
      (node (ref "V6") (pin "P$1") (pinfunction "P$1_P$1") (pintype "bidirectional"))
    )
    (net (code "110") (name "Z_N") (class "Default")
      (node (ref "D4") (pin "A") (pinfunction "A_A") (pintype "bidirectional"))
      (node (ref "R9") (pin "1") (pinfunction "1_1") (pintype "passive"))
      (node (ref "V5") (pin "P$1") (pinfunction "P$1_P$1") (pintype "bidirectional"))
    )
    (net (code "111") (name "Z_P") (class "Default")
      (node (ref "D3") (pin "A") (pinfunction "A_A") (pintype "bidirectional"))
      (node (ref "R8") (pin "1") (pinfunction "1_1") (pintype "passive"))
      (node (ref "V4") (pin "P$1") (pinfunction "P$1_P$1") (pintype "bidirectional"))
    )
    (net (code "112") (name "unconnected-(U$6-P03-PadP$7)") (class "Default")
      (node (ref "U$6") (pin "P$7") (pinfunction "P03_P$7") (pintype "bidirectional"))
    )
    (net (code "113") (name "~{BATT_INT}") (class "Default")
      (node (ref "R84") (pin "1") (pinfunction "1_1") (pintype "passive"))
      (node (ref "U$6") (pin "P$1") (pinfunction "~{INT}_P$1") (pintype "bidirectional"))
      (node (ref "V11") (pin "P$1") (pinfunction "P$1_P$1") (pintype "bidirectional"))
    )
  )
)
